# ESP32-_3_5_TFT_Display_SPI_V1_0_20230116.net
KiCad netlist of a schematic drawn in EAGLE
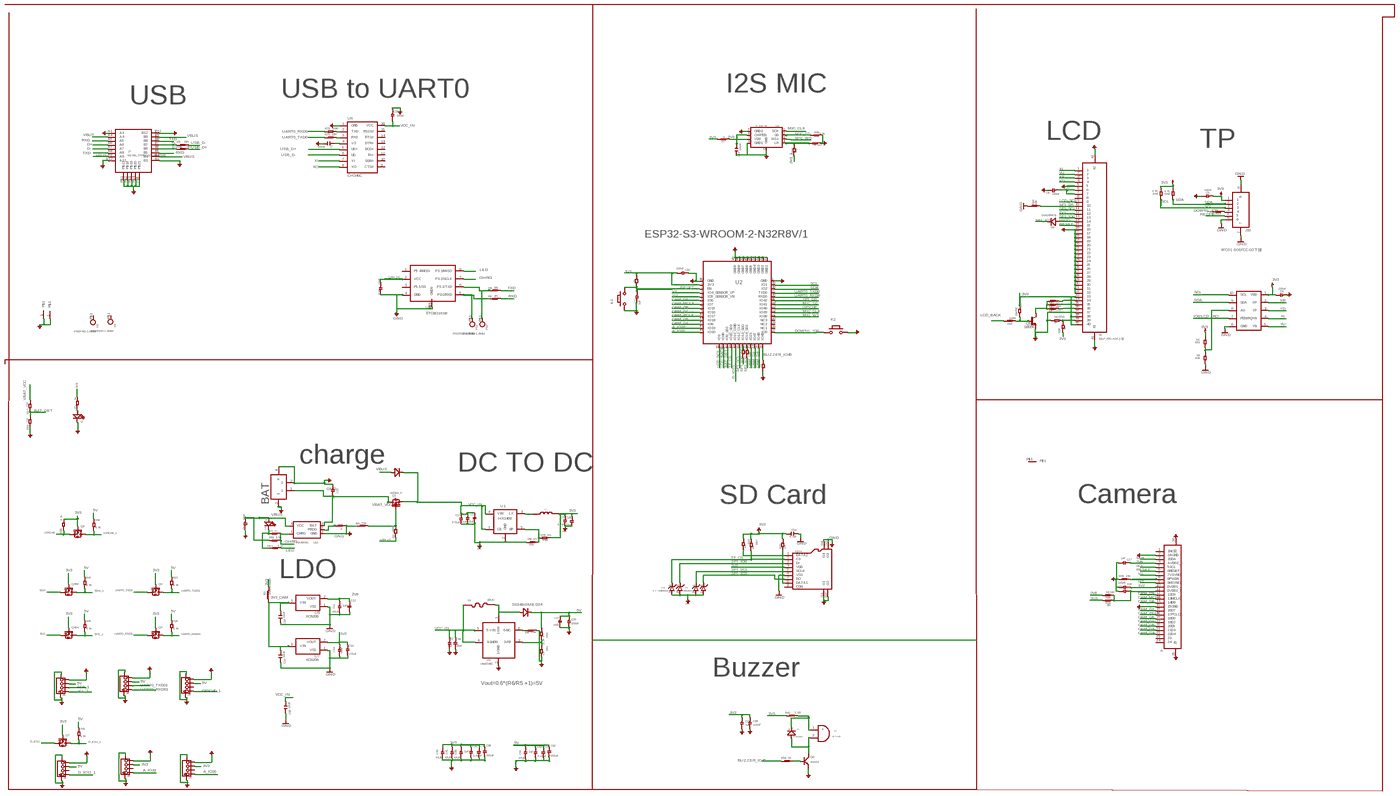
[diagram p0: schematic, sheet 1, overview]
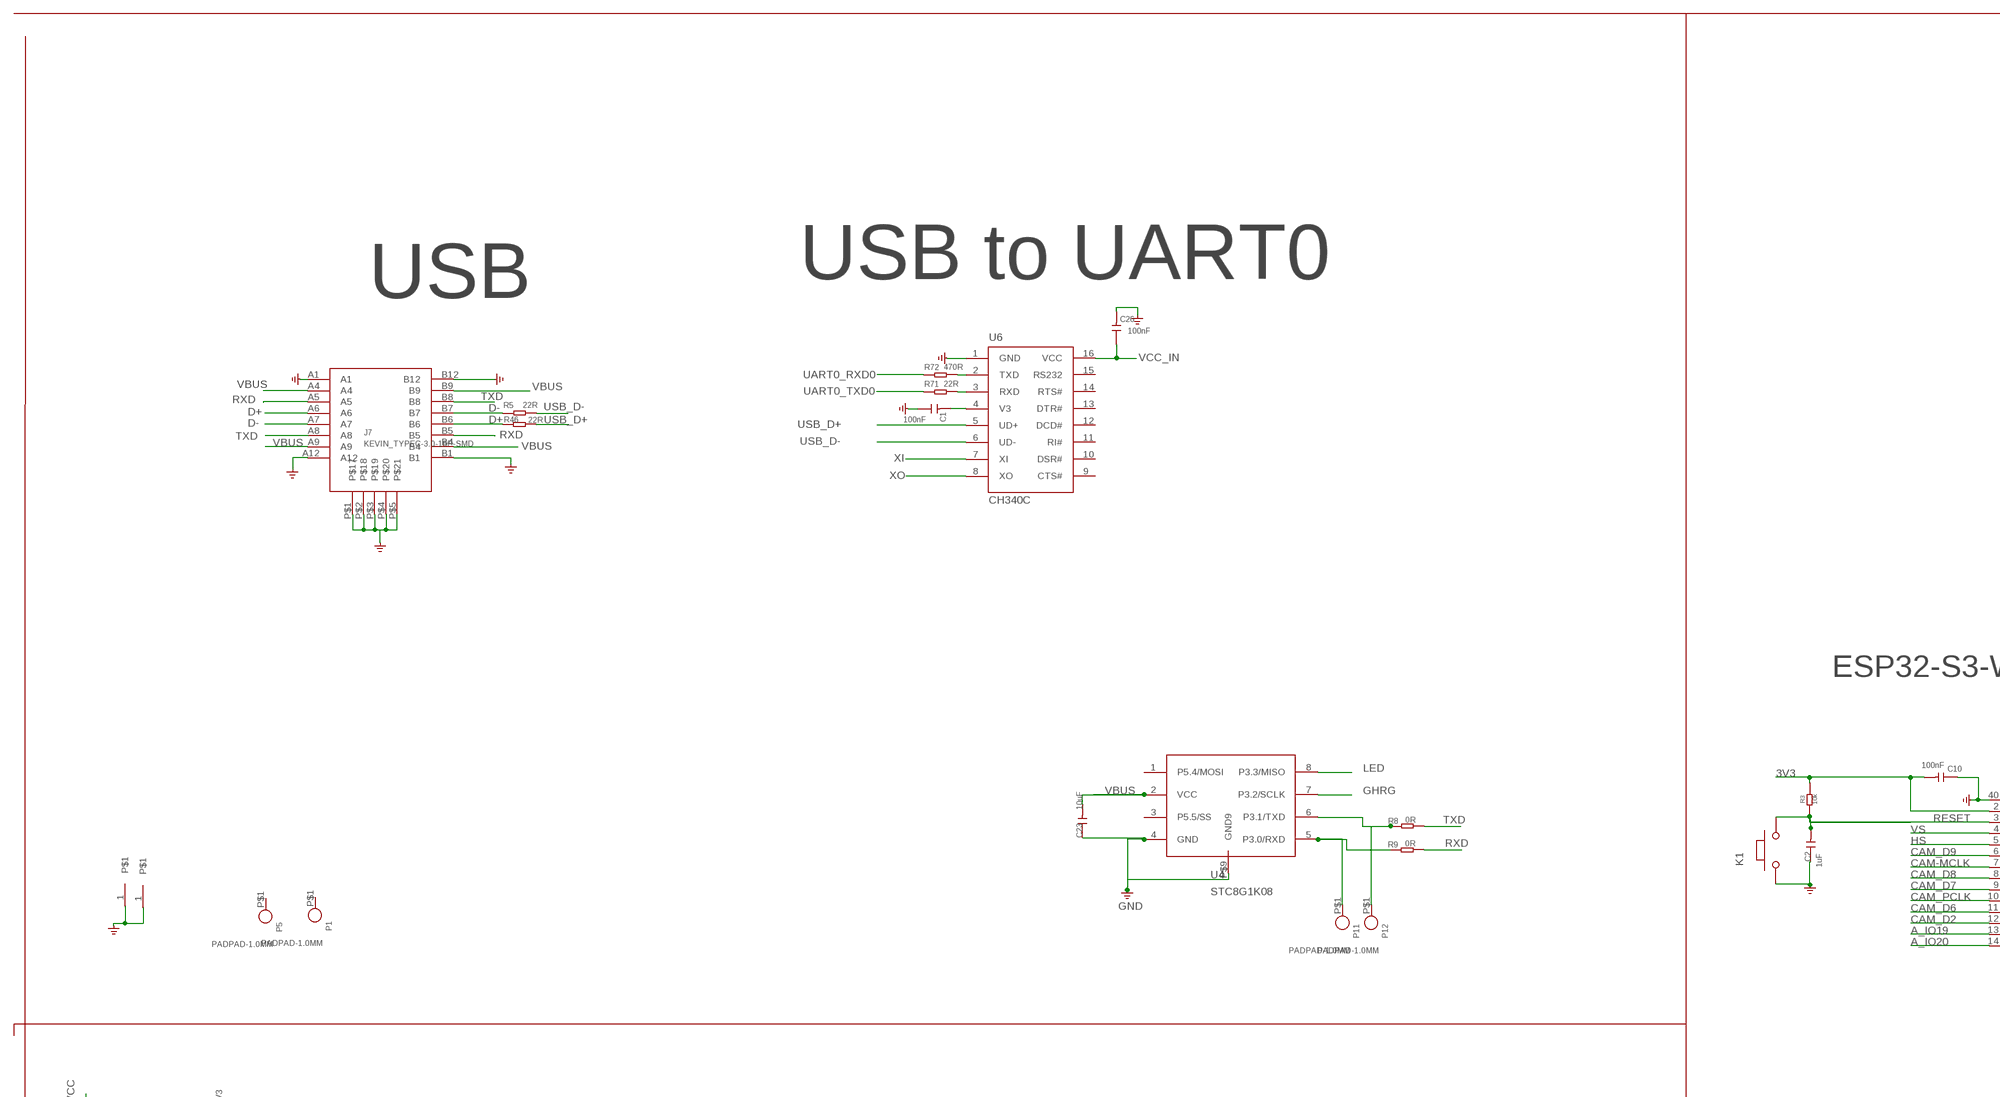
[diagram p1: schematic, sheet 1, part 1 of 4]
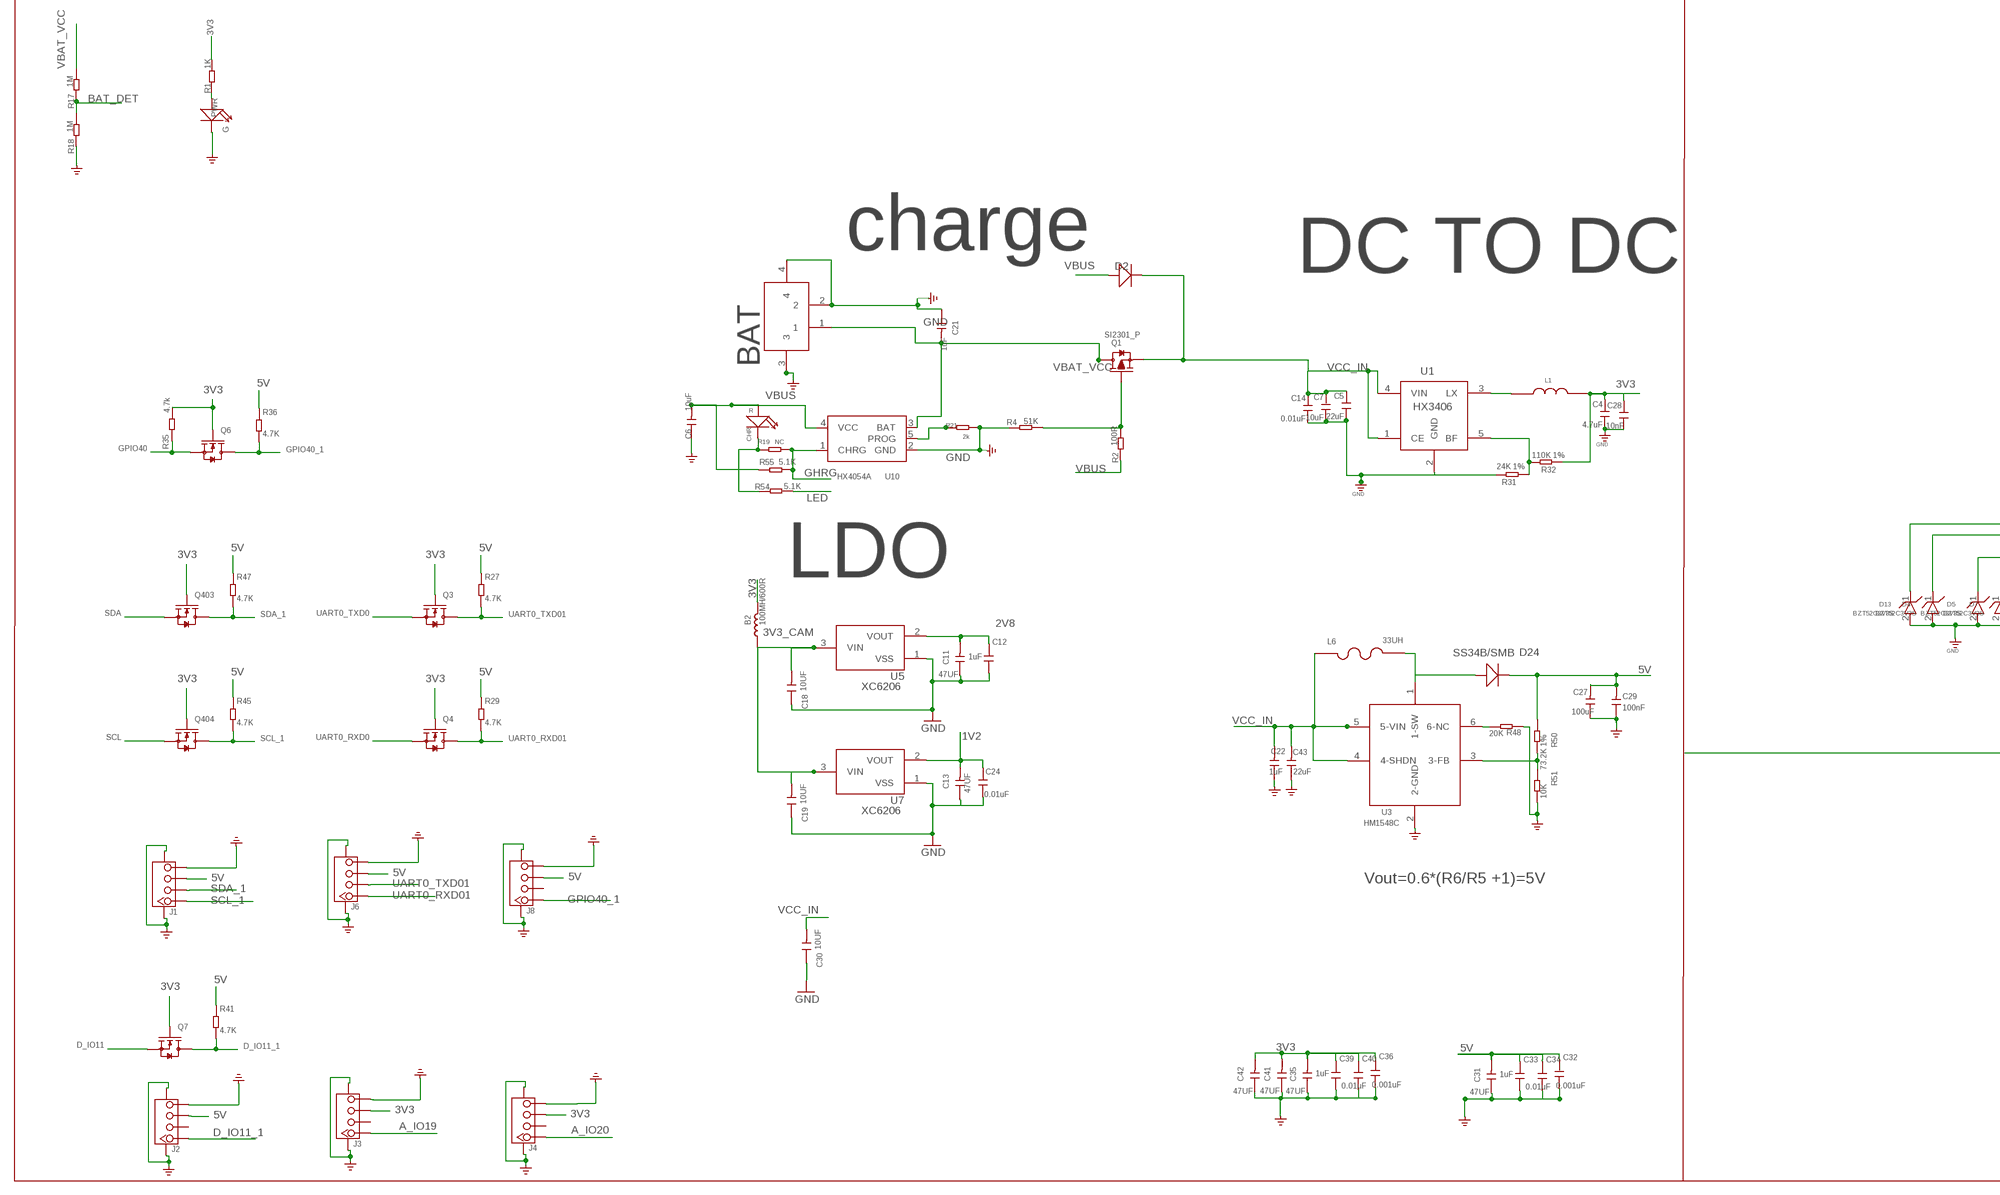
[diagram p2: schematic, sheet 1, part 2 of 4]
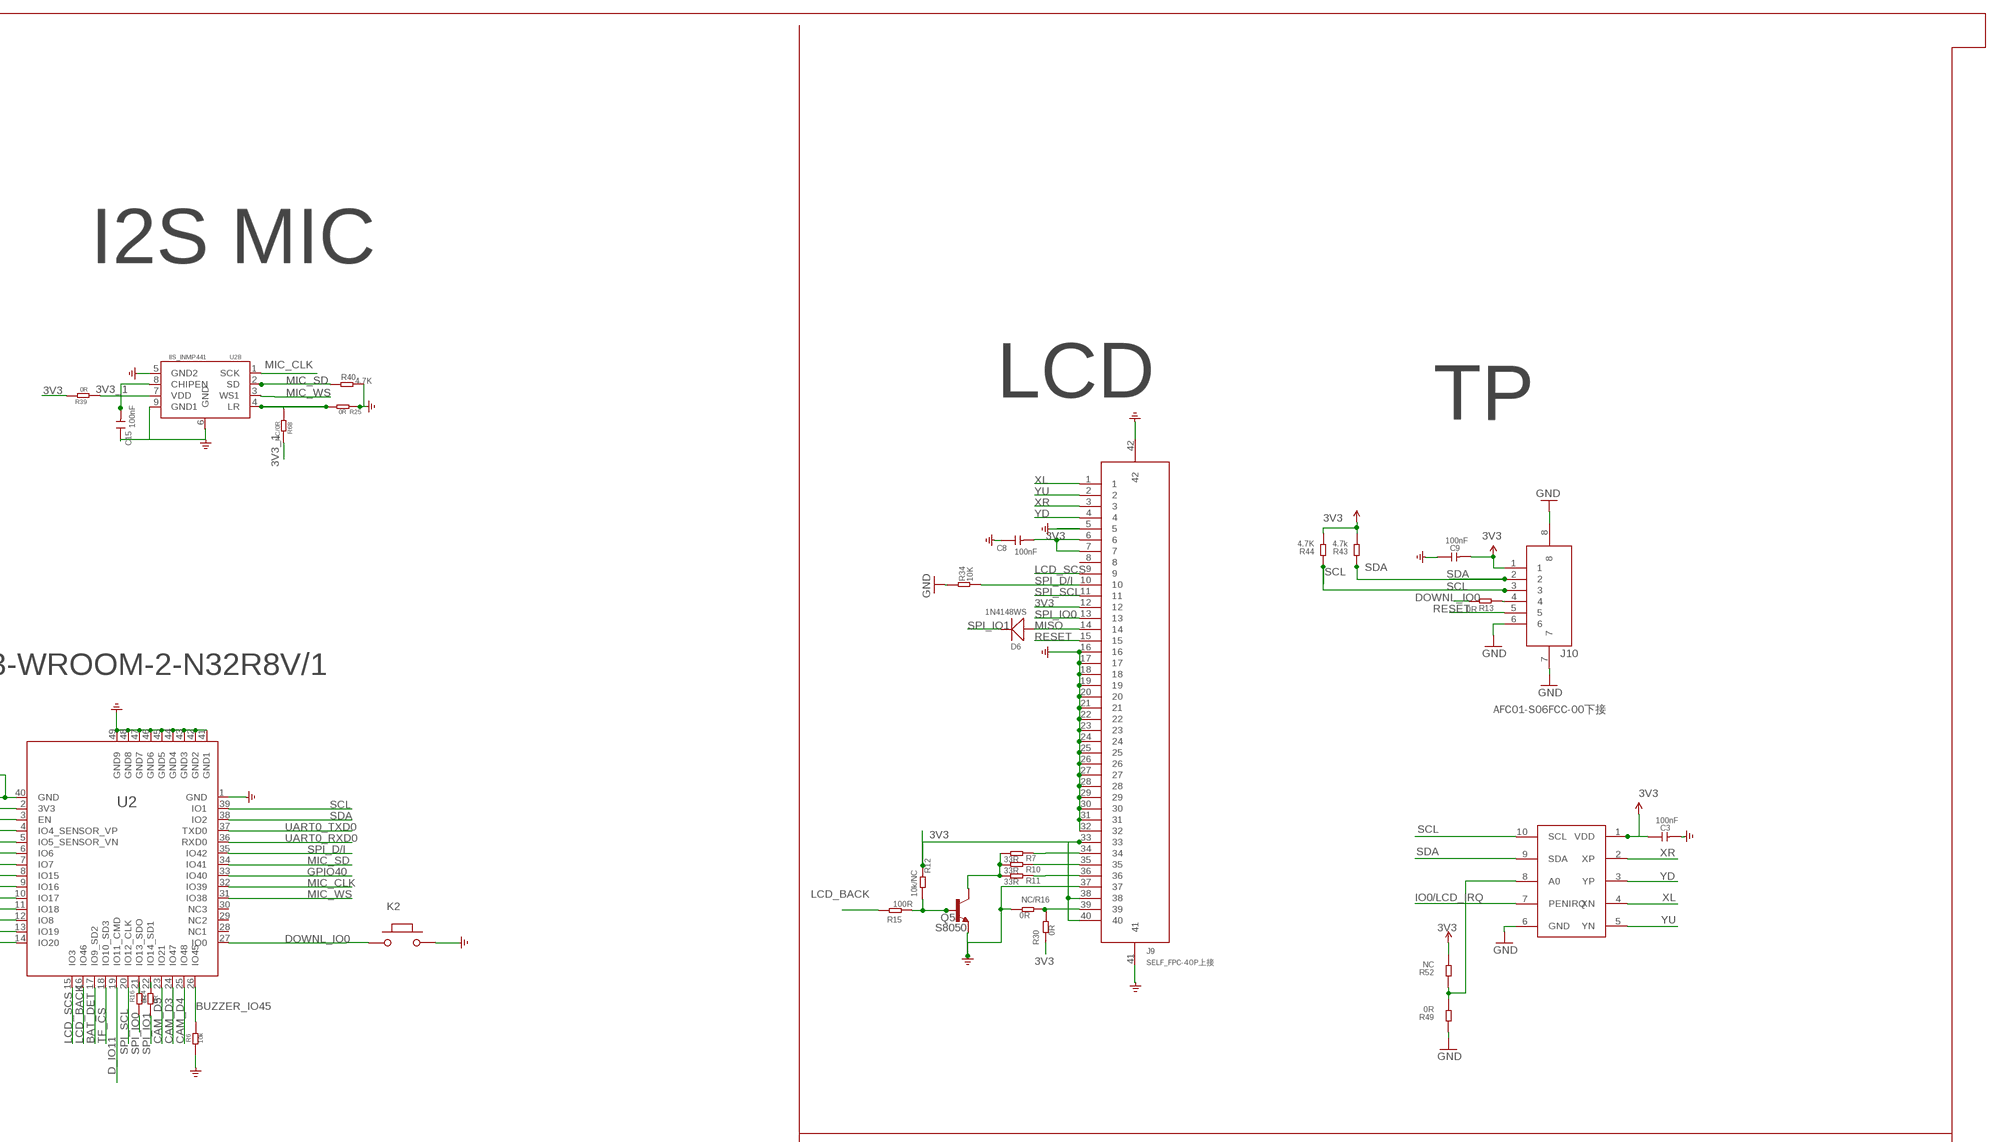
[diagram p3: schematic, sheet 1, part 3 of 4]
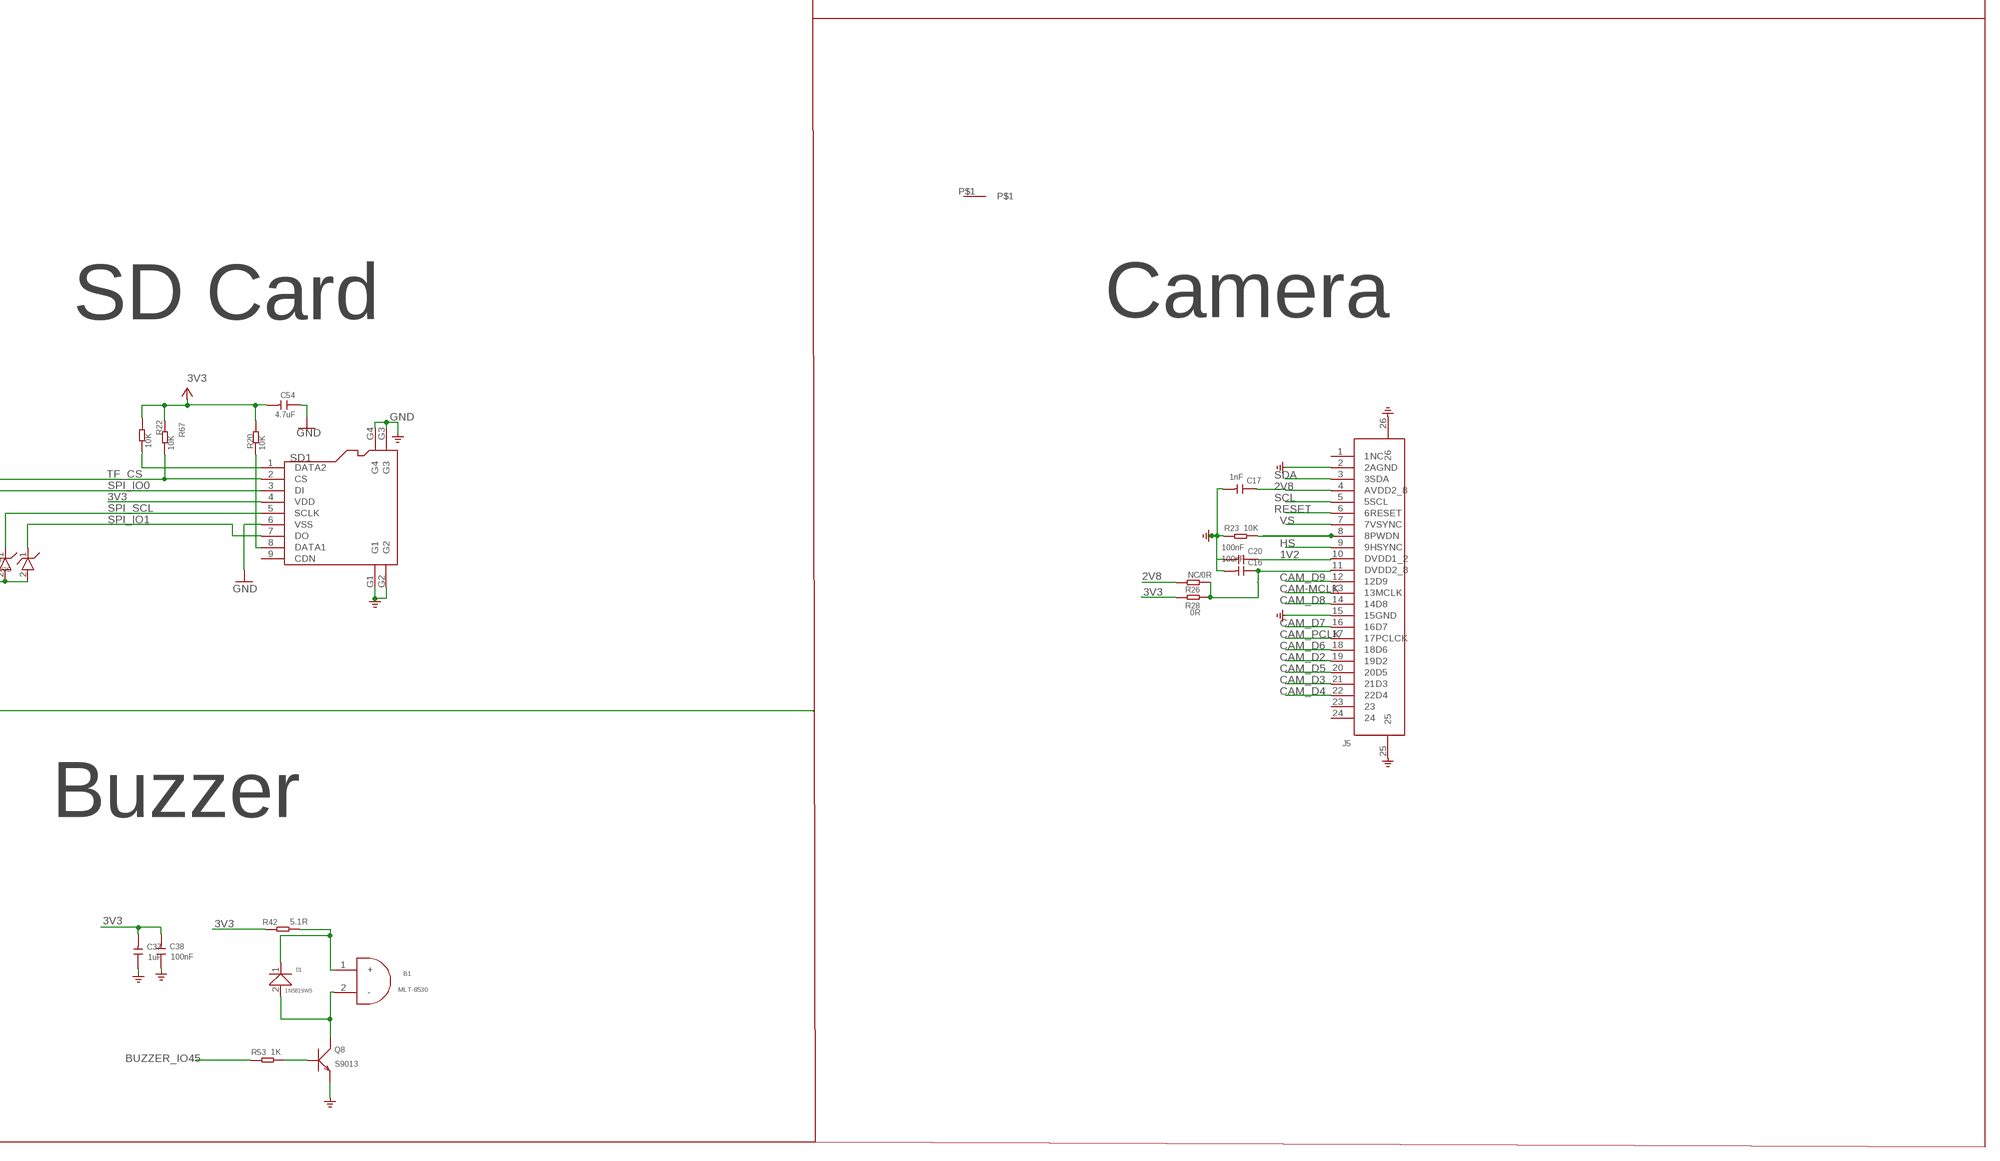
[diagram p4: schematic, sheet 1, part 4 of 4]

(export (version "E")
  (design (tool "Eeschema 10.0.6"))
  (components
    (comp (ref "B1")
      (value "MLT-8530")
      (footprint "eagle-import:MLT-8530")
      (libsource (lib "eagle-import") (part "MLT-8530"))
    )
    (comp (ref "B2")
      (value "100MH/600R")
      (footprint "eagle-import:0805@1")
      (libsource (lib "eagle-import") (part "L0805"))
    )
    (comp (ref "BAT")
      (value "CON-80-2P-M")
      (footprint "eagle-import:2P-2.0-M")
      (libsource (lib "eagle-import") (part "CON-80-2P-M"))
    )
    (comp (ref "C1")
      (value "100nF")
      (footprint "eagle-import:0603")
      (libsource (lib "eagle-import") (part "C0603"))
    )
    (comp (ref "C2")
      (value "1uF")
      (footprint "eagle-import:C0603")
      (libsource (lib "eagle-import") (part "C-0603"))
    )
    (comp (ref "C3")
      (value "100nF")
      (footprint "eagle-import:C0603")
      (libsource (lib "eagle-import") (part "C-0603"))
    )
    (comp (ref "C4")
      (value "4.7uF")
      (footprint "eagle-import:0603")
      (libsource (lib "eagle-import") (part "cooper_C0603"))
    )
    (comp (ref "C5")
      (value "22uF")
      (footprint "eagle-import:0603")
      (libsource (lib "eagle-import") (part "cooper_C0603"))
    )
    (comp (ref "C6")
      (value "10uF")
      (footprint "eagle-import:C0603")
      (libsource (lib "eagle-import") (part "C-0603"))
    )
    (comp (ref "C7")
      (value "10uF")
      (footprint "eagle-import:0603")
      (libsource (lib "eagle-import") (part "cooper_C0603"))
    )
    (comp (ref "C8")
      (value "100nF")
      (footprint "eagle-import:C0603")
      (libsource (lib "eagle-import") (part "C-0603"))
    )
    (comp (ref "C9")
      (value "100nF")
      (footprint "eagle-import:C0603")
      (libsource (lib "eagle-import") (part "C-0603"))
    )
    (comp (ref "C10")
      (value "100nF")
      (footprint "eagle-import:C0603")
      (libsource (lib "eagle-import") (part "C-0603"))
    )
    (comp (ref "C11")
      (value "47UF")
      (footprint "eagle-import:1206")
      (libsource (lib "eagle-import") (part "C1206"))
    )
    (comp (ref "C12")
      (value "1uF")
      (footprint "eagle-import:0603")
      (libsource (lib "eagle-import") (part "cooper_C0603"))
    )
    (comp (ref "C13")
      (value "47UF")
      (footprint "eagle-import:1206")
      (libsource (lib "eagle-import") (part "C1206"))
    )
    (comp (ref "C14")
      (value "0.01uF")
      (footprint "eagle-import:0603")
      (libsource (lib "eagle-import") (part "cooper_C0603"))
    )
    (comp (ref "C15")
      (value "100nF")
      (footprint "eagle-import:C0603")
      (libsource (lib "eagle-import") (part "C-0603"))
    )
    (comp (ref "C16")
      (value "100nF")
      (footprint "eagle-import:C0603")
      (libsource (lib "eagle-import") (part "C-0603"))
    )
    (comp (ref "C17")
      (value "1nF")
      (footprint "eagle-import:C0603")
      (libsource (lib "eagle-import") (part "C-0603"))
    )
    (comp (ref "C18")
      (value "10UF")
      (footprint "eagle-import:C0603")
      (libsource (lib "eagle-import") (part "C-0603"))
    )
    (comp (ref "C19")
      (value "10UF")
      (footprint "eagle-import:C0603")
      (libsource (lib "eagle-import") (part "C-0603"))
    )
    (comp (ref "C20")
      (value "100nF")
      (footprint "eagle-import:C0603")
      (libsource (lib "eagle-import") (part "C-0603"))
    )
    (comp (ref "C21")
      (value "1uF")
      (footprint "eagle-import:C0603")
      (libsource (lib "eagle-import") (part "C-0603"))
    )
    (comp (ref "C22")
      (value "1uF")
      (footprint "eagle-import:0603")
      (libsource (lib "eagle-import") (part "C0603"))
    )
    (comp (ref "C23")
      (value "10uF")
      (footprint "eagle-import:C0603")
      (libsource (lib "eagle-import") (part "C-0603"))
    )
    (comp (ref "C24")
      (value "0.01uF")
      (footprint "eagle-import:0603")
      (libsource (lib "eagle-import") (part "cooper_C0603"))
    )
    (comp (ref "C26")
      (value "100nF")
      (footprint "eagle-import:0603")
      (libsource (lib "eagle-import") (part "C0603"))
    )
    (comp (ref "C27")
      (value "100uF")
      (footprint "eagle-import:0805")
      (libsource (lib "eagle-import") (part "C0805"))
    )
    (comp (ref "C28")
      (value "10nF")
      (footprint "eagle-import:0603")
      (libsource (lib "eagle-import") (part "cooper_C0603"))
    )
    (comp (ref "C29")
      (value "100nF")
      (footprint "eagle-import:0603")
      (libsource (lib "eagle-import") (part "C0603"))
    )
    (comp (ref "C30")
      (value "10UF")
      (footprint "eagle-import:C0603")
      (libsource (lib "eagle-import") (part "C-0603"))
    )
    (comp (ref "C31")
      (value "47UF")
      (footprint "eagle-import:1206")
      (libsource (lib "eagle-import") (part "C1206"))
    )
    (comp (ref "C32")
      (value "0.001uF")
      (footprint "eagle-import:0603")
      (libsource (lib "eagle-import") (part "cooper_C0603"))
    )
    (comp (ref "C33")
      (value "1uF")
      (footprint "eagle-import:0603")
      (libsource (lib "eagle-import") (part "cooper_C0603"))
    )
    (comp (ref "C34")
      (value "0.01uF")
      (footprint "eagle-import:0603")
      (libsource (lib "eagle-import") (part "cooper_C0603"))
    )
    (comp (ref "C35")
      (value "47UF")
      (footprint "eagle-import:1206")
      (libsource (lib "eagle-import") (part "C1206"))
    )
    (comp (ref "C36")
      (value "0.001uF")
      (footprint "eagle-import:0603")
      (libsource (lib "eagle-import") (part "cooper_C0603"))
    )
    (comp (ref "C37")
      (value "1uF")
      (footprint "eagle-import:DISCRETE_C0603")
      (libsource (lib "eagle-import") (part "A_xbj_DISCRETE_C-0603"))
    )
    (comp (ref "C38")
      (value "100nF")
      (footprint "eagle-import:DISCRETE_C0603")
      (libsource (lib "eagle-import") (part "A_xbj_DISCRETE_C-0603"))
    )
    (comp (ref "C39")
      (value "1uF")
      (footprint "eagle-import:0603")
      (libsource (lib "eagle-import") (part "cooper_C0603"))
    )
    (comp (ref "C40")
      (value "0.01uF")
      (footprint "eagle-import:0603")
      (libsource (lib "eagle-import") (part "cooper_C0603"))
    )
    (comp (ref "C41")
      (value "47UF")
      (footprint "eagle-import:1206")
      (libsource (lib "eagle-import") (part "C1206"))
    )
    (comp (ref "C42")
      (value "47UF")
      (footprint "eagle-import:1206")
      (libsource (lib "eagle-import") (part "C1206"))
    )
    (comp (ref "C43")
      (value "22uF")
      (footprint "eagle-import:0805")
      (libsource (lib "eagle-import") (part "C0805"))
    )
    (comp (ref "C54")
      (value "4.7uF")
      (footprint "eagle-import:DISCRETE_C0603")
      (libsource (lib "eagle-import") (part "DISCRETE_C-0603"))
    )
    (comp (ref "CHR")
      (value "R")
      (footprint "eagle-import:D0603")
      (libsource (lib "eagle-import") (part "007-LED0603"))
    )
    (comp (ref "D1")
      (value "1N5819WS")
      (footprint "eagle-import:SOD-323")
      (libsource (lib "eagle-import") (part "1N5819WS"))
    )
    (comp (ref "D2")
      (value "1N5819/S0D-123")
      (footprint "eagle-import:1206-1")
      (libsource (lib "eagle-import") (part "D'1N4148-SMD'"))
    )
    (comp (ref "D4")
      (value "BZT52C3V3S")
      (footprint "eagle-import:SOD-323@1")
      (libsource (lib "eagle-import") (part "BZT52C3V3S"))
    )
    (comp (ref "D5")
      (value "BZT52C3V3S")
      (footprint "eagle-import:SOD-323@1")
      (libsource (lib "eagle-import") (part "BZT52C3V3S"))
    )
    (comp (ref "D6")
      (value "1N4148WS")
      (footprint "eagle-import:SOD323")
      (libsource (lib "eagle-import") (part "D'0805'"))
    )
    (comp (ref "D7")
      (value "BZT52C3V3S")
      (footprint "eagle-import:SOD-323@1")
      (libsource (lib "eagle-import") (part "BZT52C3V3S"))
    )
    (comp (ref "D13")
      (value "BZT52C3V3S")
      (footprint "eagle-import:SOD-323@1")
      (libsource (lib "eagle-import") (part "BZT52C3V3S"))
    )
    (comp (ref "D24")
      (value "SS34B/SMB")
      (footprint "eagle-import:214AB")
      (libsource (lib "eagle-import") (part "214ABDO-214AB"))
    )
    (comp (ref "J1")
      (value "TWIG-4P-2.0-SMD-FEMALE-REINFORCE'90D'")
      (footprint "eagle-import:4P-SMD-2.0-90D")
      (libsource (lib "eagle-import") (part "TWIG-4P-2.0-SMD-FEMALE-REINFORCE'90D'"))
    )
    (comp (ref "J2")
      (value "TWIG-4P-2.0-SMD-FEMALE-REINFORCE'90D'")
      (footprint "eagle-import:4P-SMD-2.0-90D")
      (libsource (lib "eagle-import") (part "TWIG-4P-2.0-SMD-FEMALE-REINFORCE'90D'"))
    )
    (comp (ref "J3")
      (value "TWIG-4P-2.0-SMD-FEMALE-REINFORCE'90D'")
      (footprint "eagle-import:4P-SMD-2.0-90D")
      (libsource (lib "eagle-import") (part "TWIG-4P-2.0-SMD-FEMALE-REINFORCE'90D'"))
    )
    (comp (ref "J4")
      (value "TWIG-4P-2.0-SMD-FEMALE-REINFORCE'90D'")
      (footprint "eagle-import:4P-SMD-2.0-90D")
      (libsource (lib "eagle-import") (part "TWIG-4P-2.0-SMD-FEMALE-REINFORCE'90D'"))
    )
    (comp (ref "J5")
      (value "SMD_HEADERP_24PX0.5上接")
      (footprint "eagle-import:SMD_HEADERP_24PX0.5")
      (libsource (lib "eagle-import") (part "SMD_HEADERP_24PX0.5"))
    )
    (comp (ref "J6")
      (value "TWIG-4P-2.0-SMD-FEMALE-REINFORCE'90D'")
      (footprint "eagle-import:4P-SMD-2.0-90D")
      (libsource (lib "eagle-import") (part "TWIG-4P-2.0-SMD-FEMALE-REINFORCE'90D'"))
    )
    (comp (ref "J7")
      (value "KEVIN_TYPEC-3.0-16P-SMD")
      (footprint "eagle-import:KEVIN_3.0TYPEC-SMD")
      (libsource (lib "eagle-import") (part "KEVIN_TYPEC-3.0-16P-SMD"))
    )
    (comp (ref "J8")
      (value "TWIG-4P-2.0-SMD-FEMALE-REINFORCE'90D'")
      (footprint "eagle-import:4P-SMD-2.0-90D")
      (libsource (lib "eagle-import") (part "TWIG-4P-2.0-SMD-FEMALE-REINFORCE'90D'"))
    )
    (comp (ref "J9")
      (value "SELF_FPC-40P上接")
      (footprint "eagle-import:SELF_SMD42-50P-2560L490W")
      (libsource (lib "eagle-import") (part "SELF_FPC-40P"))
    )
    (comp (ref "J10")
      (value "AFC01-S06FCC-00下接")
      (footprint "eagle-import:SMD8-50P-740L535W")
      (libsource (lib "eagle-import") (part "AFC01-S06FCC-00"))
    )
    (comp (ref "K1")
      (value "BUTTON")
      (footprint "eagle-import:157SW")
      (libsource (lib "eagle-import") (part "PB157"))
    )
    (comp (ref "K2")
      (value "BUTTON")
      (footprint "eagle-import:157SW")
      (libsource (lib "eagle-import") (part "PB157"))
    )
    (comp (ref "L1")
      (value "CD32_10uH")
      (footprint "eagle-import:CD32")
      (libsource (lib "eagle-import") (part "CD32_950MA"))
    )
    (comp (ref "L6")
      (value "33UH")
      (footprint "eagle-import:L773")
      (libsource (lib "eagle-import") (part "L-773"))
    )
    (comp (ref "NC/R16")
      (value "0R")
      (footprint "eagle-import:R0603")
      (libsource (lib "eagle-import") (part "cooper_R0603"))
    )
    (comp (ref "P1")
      (value "PADPAD-1.0MM")
      (footprint "eagle-import:PAD-1.0MM")
      (libsource (lib "eagle-import") (part "PADPAD-1.0MM"))
    )
    (comp (ref "P3")
      (value "3M-5")
      (footprint "eagle-import:3M-5")
      (libsource (lib "eagle-import") (part "3M-5"))
    )
    (comp (ref "P4")
      (value "3M-5")
      (footprint "eagle-import:3M-5")
      (libsource (lib "eagle-import") (part "3M-5"))
    )
    (comp (ref "P5")
      (value "PADPAD-1.0MM")
      (footprint "eagle-import:PAD-1.0MM")
      (libsource (lib "eagle-import") (part "PADPAD-1.0MM"))
    )
    (comp (ref "P11")
      (value "PADPAD-1.0MM")
      (footprint "eagle-import:PAD-1.0MM")
      (libsource (lib "eagle-import") (part "PADPAD-1.0MM"))
    )
    (comp (ref "P12")
      (value "PADPAD-1.0MM")
      (footprint "eagle-import:PAD-1.0MM")
      (libsource (lib "eagle-import") (part "PADPAD-1.0MM"))
    )
    (comp (ref "PWR")
      (value "G")
      (footprint "eagle-import:LED-0603")
      (libsource (lib "eagle-import") (part "LED'0603'"))
    )
    (comp (ref "Q1")
      (value "SI2301_P")
      (footprint "eagle-import:DISCRETE_SOT23")
      (libsource (lib "eagle-import") (part "DISCRETE_MOSFET-PSOT23"))
    )
    (comp (ref "Q3")
      (value "MOSFET-N'SOT23'")
      (footprint "eagle-import:SOT23")
      (libsource (lib "eagle-import") (part "MOSFET-N'SOT23'"))
    )
    (comp (ref "Q4")
      (value "MOSFET-N'SOT23'")
      (footprint "eagle-import:SOT23")
      (libsource (lib "eagle-import") (part "MOSFET-N'SOT23'"))
    )
    (comp (ref "Q5")
      (value "S8050")
      (footprint "eagle-import:SPARKFUN_SOT23")
      (libsource (lib "eagle-import") (part "SPARKFUN_TRANSISTOR_NPNSOT23"))
    )
    (comp (ref "Q6")
      (value "MOSFET-N'SOT23'")
      (footprint "eagle-import:SOT23")
      (libsource (lib "eagle-import") (part "MOSFET-N'SOT23'"))
    )
    (comp (ref "Q7")
      (value "MOSFET-N'SOT23'")
      (footprint "eagle-import:SOT23")
      (libsource (lib "eagle-import") (part "MOSFET-N'SOT23'"))
    )
    (comp (ref "Q8")
      (value "S9013")
      (footprint "eagle-import:SOT23@1")
      (libsource (lib "eagle-import") (part "TRANSISTOR-NPN-SOT23"))
    )
    (comp (ref "Q403")
      (value "MOSFET-N'SOT23'")
      (footprint "eagle-import:SOT23")
      (libsource (lib "eagle-import") (part "MOSFET-N'SOT23'"))
    )
    (comp (ref "Q404")
      (value "MOSFET-N'SOT23'")
      (footprint "eagle-import:SOT23")
      (libsource (lib "eagle-import") (part "MOSFET-N'SOT23'"))
    )
    (comp (ref "R1")
      (value "1K")
      (footprint "eagle-import:R0603")
      (libsource (lib "eagle-import") (part "R-0603"))
    )
    (comp (ref "R2")
      (value "100R")
      (footprint "eagle-import:R0603")
      (libsource (lib "eagle-import") (part "cooper_R0603"))
    )
    (comp (ref "R3")
      (value "10k")
      (footprint "eagle-import:R0603")
      (libsource (lib "eagle-import") (part "R-0603"))
    )
    (comp (ref "R4")
      (value "51K")
      (footprint "eagle-import:R0603")
      (libsource (lib "eagle-import") (part "cooper_R0603"))
    )
    (comp (ref "R5")
      (value "22R")
      (footprint "eagle-import:DISCRETE_R0603")
      (libsource (lib "eagle-import") (part "Crowtail-_LED-V2.0-20190615-01_DISCRETE_R-0603"))
    )
    (comp (ref "R6")
      (value "10k")
      (footprint "eagle-import:R0603")
      (libsource (lib "eagle-import") (part "R-0603"))
    )
    (comp (ref "R7")
      (value "33R")
      (footprint "eagle-import:R0603")
      (libsource (lib "eagle-import") (part "cooper_R0603"))
    )
    (comp (ref "R8")
      (value "0R")
      (footprint "eagle-import:R0603")
      (libsource (lib "eagle-import") (part "cooper_R0603"))
    )
    (comp (ref "R9")
      (value "0R")
      (footprint "eagle-import:R0603")
      (libsource (lib "eagle-import") (part "cooper_R0603"))
    )
    (comp (ref "R10")
      (value "33R")
      (footprint "eagle-import:R0603")
      (libsource (lib "eagle-import") (part "cooper_R0603"))
    )
    (comp (ref "R11")
      (value "33R")
      (footprint "eagle-import:R0603")
      (libsource (lib "eagle-import") (part "cooper_R0603"))
    )
    (comp (ref "R12")
      (value "10k/NC")
      (footprint "eagle-import:R0603")
      (libsource (lib "eagle-import") (part "cooper_R0603"))
    )
    (comp (ref "R13")
      (value "0R")
      (footprint "eagle-import:DISCRETE_R0603")
      (libsource (lib "eagle-import") (part "DISCRETE_R-0603"))
    )
    (comp (ref "R15")
      (value "100R")
      (footprint "eagle-import:R0603")
      (libsource (lib "eagle-import") (part "cooper_R0603"))
    )
    (comp (ref "R16")
      (value "0R")
      (footprint "eagle-import:R0603")
      (libsource (lib "eagle-import") (part "R-0603"))
    )
    (comp (ref "R17")
      (value "1M")
      (footprint "eagle-import:R0603")
      (libsource (lib "eagle-import") (part "cooper_R0603"))
    )
    (comp (ref "R18")
      (value "1M")
      (footprint "eagle-import:R0603")
      (libsource (lib "eagle-import") (part "cooper_R0603"))
    )
    (comp (ref "R19")
      (value "NC")
      (footprint "eagle-import:R0603")
      (libsource (lib "eagle-import") (part "R-0603"))
    )
    (comp (ref "R20")
      (value "10K")
      (footprint "eagle-import:DISCRETE_R0603")
      (libsource (lib "eagle-import") (part "Crowtail-_LED-V2.0-20190615-01_DISCRETE_R-0603"))
    )
    (comp (ref "R21")
      (value "2k")
      (footprint "eagle-import:R0603")
      (libsource (lib "eagle-import") (part "R-0603"))
    )
    (comp (ref "R22")
      (value "10K")
      (footprint "eagle-import:DISCRETE_R0603")
      (libsource (lib "eagle-import") (part "Crowtail-_LED-V2.0-20190615-01_DISCRETE_R-0603"))
    )
    (comp (ref "R23")
      (value "10K")
      (footprint "eagle-import:DISCRETE_R0603")
      (libsource (lib "eagle-import") (part "Crowtail-_LED-V2.0-20190615-01_DISCRETE_R-0603"))
    )
    (comp (ref "R24")
      (value "0R")
      (footprint "eagle-import:R0603")
      (libsource (lib "eagle-import") (part "R-0603"))
    )
    (comp (ref "R25")
      (value "0R")
      (footprint "eagle-import:R0603")
      (libsource (lib "eagle-import") (part "R-0603"))
    )
    (comp (ref "R26")
      (value "NC/0R")
      (footprint "eagle-import:R0603")
      (libsource (lib "eagle-import") (part "cooper_R0603"))
    )
    (comp (ref "R27")
      (value "4.7K")
      (footprint "eagle-import:R0603")
      (libsource (lib "eagle-import") (part "cooper_R0603"))
    )
    (comp (ref "R28")
      (value "0R")
      (footprint "eagle-import:R0603")
      (libsource (lib "eagle-import") (part "cooper_R0603"))
    )
    (comp (ref "R29")
      (value "4.7K")
      (footprint "eagle-import:R0603")
      (libsource (lib "eagle-import") (part "cooper_R0603"))
    )
    (comp (ref "R30")
      (value "0R")
      (footprint "eagle-import:R0603")
      (libsource (lib "eagle-import") (part "cooper_R0603"))
    )
    (comp (ref "R31")
      (value "24K 1%")
      (footprint "eagle-import:R0603")
      (libsource (lib "eagle-import") (part "cooper_R0603"))
    )
    (comp (ref "R32")
      (value "110K 1%")
      (footprint "eagle-import:R0603")
      (libsource (lib "eagle-import") (part "cooper_R0603"))
    )
    (comp (ref "R34")
      (value "10K")
      (footprint "eagle-import:DISCRETE_R0603")
      (libsource (lib "eagle-import") (part "DISCRETE_R-0603"))
    )
    (comp (ref "R35")
      (value "4.7k")
      (footprint "eagle-import:R0603")
      (libsource (lib "eagle-import") (part "cooper_R0603"))
    )
    (comp (ref "R36")
      (value "4.7K")
      (footprint "eagle-import:R0603")
      (libsource (lib "eagle-import") (part "cooper_R0603"))
    )
    (comp (ref "R39")
      (value "0R")
      (footprint "eagle-import:R0603")
      (libsource (lib "eagle-import") (part "R-0603"))
    )
    (comp (ref "R40")
      (value "4.7K")
      (footprint "eagle-import:DISCRETE_R0603")
      (libsource (lib "eagle-import") (part "Crowtail-_LED-V2.0-20190615-01_DISCRETE_R-0603"))
    )
    (comp (ref "R41")
      (value "4.7K")
      (footprint "eagle-import:R0603")
      (libsource (lib "eagle-import") (part "cooper_R0603"))
    )
    (comp (ref "R42")
      (value "5.1R")
      (footprint "eagle-import:R0603")
      (libsource (lib "eagle-import") (part "R0603"))
    )
    (comp (ref "R43")
      (value "4.7k")
      (footprint "eagle-import:DISCRETE_R0603")
      (libsource (lib "eagle-import") (part "DISCRETE_R-0603"))
    )
    (comp (ref "R44")
      (value "4.7K")
      (footprint "eagle-import:DISCRETE_R0603")
      (libsource (lib "eagle-import") (part "DISCRETE_R-0603"))
    )
    (comp (ref "R45")
      (value "4.7K")
      (footprint "eagle-import:R0603")
      (libsource (lib "eagle-import") (part "cooper_R0603"))
    )
    (comp (ref "R46")
      (value "22R")
      (footprint "eagle-import:DISCRETE_R0603")
      (libsource (lib "eagle-import") (part "Crowtail-_LED-V2.0-20190615-01_DISCRETE_R-0603"))
    )
    (comp (ref "R47")
      (value "4.7K")
      (footprint "eagle-import:R0603")
      (libsource (lib "eagle-import") (part "cooper_R0603"))
    )
    (comp (ref "R48")
      (value "20K")
      (footprint "eagle-import:DISCRETE_R0603")
      (libsource (lib "eagle-import") (part "Crowtail-_LED-V2.0-20190615-01_DISCRETE_R-0603"))
    )
    (comp (ref "R49")
      (value "0R")
      (footprint "eagle-import:DISCRETE_R0603")
      (libsource (lib "eagle-import") (part "DISCRETE_R-0603"))
    )
    (comp (ref "R50")
      (value "73.2K 1%")
      (footprint "eagle-import:DISCRETE_R0603")
      (libsource (lib "eagle-import") (part "Crowtail-_LED-V2.0-20190615-01_DISCRETE_R-0603"))
    )
    (comp (ref "R51")
      (value "10K")
      (footprint "eagle-import:DISCRETE_R0603")
      (libsource (lib "eagle-import") (part "Crowtail-_LED-V2.0-20190615-01_DISCRETE_R-0603"))
    )
    (comp (ref "R52")
      (value "NC")
      (footprint "eagle-import:DISCRETE_R0603")
      (libsource (lib "eagle-import") (part "DISCRETE_R-0603"))
    )
    (comp (ref "R53")
      (value "1K")
      (footprint "eagle-import:DISCRETE_R0603")
      (libsource (lib "eagle-import") (part "Crowtail-_LED-V2.0-20190615-01_DISCRETE_R-0603"))
    )
    (comp (ref "R54")
      (value "5.1K")
      (footprint "eagle-import:DISCRETE_R0603")
      (libsource (lib "eagle-import") (part "Crowtail-_LED-V2.0-20190615-01_DISCRETE_R-0603"))
    )
    (comp (ref "R55")
      (value "5.1K")
      (footprint "eagle-import:DISCRETE_R0603")
      (libsource (lib "eagle-import") (part "Crowtail-_LED-V2.0-20190615-01_DISCRETE_R-0603"))
    )
    (comp (ref "R67")
      (value "10K")
      (footprint "eagle-import:DISCRETE_R0603")
      (libsource (lib "eagle-import") (part "Crowtail-_LED-V2.0-20190615-01_DISCRETE_R-0603"))
    )
    (comp (ref "R68")
      (value "NC/0R")
      (footprint "eagle-import:R0603")
      (libsource (lib "eagle-import") (part "R-0603"))
    )
    (comp (ref "R71")
      (value "22R")
      (footprint "eagle-import:DISCRETE_R0603")
      (libsource (lib "eagle-import") (part "Crowtail-_LED-V2.0-20190615-01_DISCRETE_R-0603"))
    )
    (comp (ref "R72")
      (value "470R")
      (footprint "eagle-import:DISCRETE_R0603")
      (libsource (lib "eagle-import") (part "Crowtail-_LED-V2.0-20190615-01_DISCRETE_R-0603"))
    )
    (comp (ref "SD1")
      (value "HOLDER-MICROSD-9P")
      (footprint "eagle-import:9P-SMD-W_-RING")
      (libsource (lib "eagle-import") (part "HOLDER-MICROSD-9P"))
    )
    (comp (ref "U$63")
      (value "TFT-3.5")
      (footprint "eagle-import:LCD3.5寸")
      (libsource (lib "eagle-import") (part "TFT-3.5"))
    )
    (comp (ref "U1")
      (value "HX3406")
      (footprint "eagle-import:SOT23-5")
      (libsource (lib "eagle-import") (part "HX3406"))
    )
    (comp (ref "U2")
      (value "ESP32-S3-WROOM-2-N32R8V/1")
      (footprint "eagle-import:ESP32-S3-WROOM-2-N32R8V_1")
      (libsource (lib "eagle-import") (part "ESP32-S3-WROOM-2-N32R8V/1"))
    )
    (comp (ref "U3")
      (value "HM1548C")
      (footprint "eagle-import:A_XBJ_SOT23-6")
      (libsource (lib "eagle-import") (part "HM1548/SOT23-6"))
    )
    (comp (ref "U4")
      (value "STC8G1K08")
      (footprint "eagle-import:DFN8")
      (libsource (lib "eagle-import") (part "STC8G1K08"))
    )
    (comp (ref "U5")
      (value "XC6206")
      (footprint "eagle-import:SOT-23")
      (libsource (lib "eagle-import") (part "XC6206"))
    )
    (comp (ref "U6")
      (value "CH340C")
      (footprint "eagle-import:SOP-16")
      (libsource (lib "eagle-import") (part "CH340G"))
    )
    (comp (ref "U7")
      (value "XC6206")
      (footprint "eagle-import:SOT-23")
      (libsource (lib "eagle-import") (part "XC6206"))
    )
    (comp (ref "U8")
      (value "NS2009")
      (footprint "eagle-import:MSOP10")
      (libsource (lib "eagle-import") (part "NS2009"))
    )
    (comp (ref "U10")
      (value "HX4054A")
      (footprint "eagle-import:HX4054A_SOT23_5")
      (libsource (lib "eagle-import") (part "HX4054A"))
    )
    (comp (ref "U28")
      (value "IIS_INMP441")
      (footprint "eagle-import:IIS_INMP441")
      (libsource (lib "eagle-import") (part "IIS_INMP441"))
    )
  )
  (nets
    (net (code "1") (name "+3V3") (class "Default")
      (node (ref "B2") (pin "2") (pinfunction "2_2") (pintype "passive"))
      (node (ref "C10") (pin "2") (pinfunction "2_2") (pintype "passive"))
      (node (ref "C28") (pin "1") (pinfunction "1_1") (pintype "passive"))
      (node (ref "C3") (pin "1") (pinfunction "1_1") (pintype "passive"))
      (node (ref "C35") (pin "2") (pinfunction "2_2") (pintype "passive"))
      (node (ref "C36") (pin "1") (pinfunction "1_1") (pintype "passive"))
      (node (ref "C37") (pin "2") (pinfunction "2_2") (pintype "passive"))
      (node (ref "C38") (pin "2") (pinfunction "2_2") (pintype "passive"))
      (node (ref "C39") (pin "1") (pinfunction "1_1") (pintype "passive"))
      (node (ref "C4") (pin "1") (pinfunction "1_1") (pintype "passive"))
      (node (ref "C40") (pin "1") (pinfunction "1_1") (pintype "passive"))
      (node (ref "C41") (pin "2") (pinfunction "2_2") (pintype "passive"))
      (node (ref "C42") (pin "2") (pinfunction "2_2") (pintype "passive"))
      (node (ref "C54") (pin "2") (pinfunction "2_2") (pintype "passive"))
      (node (ref "C8") (pin "2") (pinfunction "2_2") (pintype "passive"))
      (node (ref "C9") (pin "2") (pinfunction "2_2") (pintype "passive"))
      (node (ref "J10") (pin "1") (pinfunction "1_1") (pintype "bidirectional"))
      (node (ref "J3") (pin "3") (pinfunction "3_3") (pintype "bidirectional"))
      (node (ref "J4") (pin "3") (pinfunction "3_3") (pintype "bidirectional"))
      (node (ref "J9") (pin "12") (pinfunction "12_12") (pintype "bidirectional"))
      (node (ref "J9") (pin "33") (pinfunction "33_33") (pintype "bidirectional"))
      (node (ref "J9") (pin "38") (pinfunction "38_38") (pintype "bidirectional"))
      (node (ref "J9") (pin "40") (pinfunction "40_40") (pintype "bidirectional"))
      (node (ref "J9") (pin "6") (pinfunction "6_6") (pintype "bidirectional"))
      (node (ref "J9") (pin "7") (pinfunction "7_7") (pintype "bidirectional"))
      (node (ref "L1") (pin "2") (pinfunction "2_2") (pintype "bidirectional"))
      (node (ref "Q3") (pin "1") (pinfunction "G_1") (pintype "passive"))
      (node (ref "Q4") (pin "1") (pinfunction "G_1") (pintype "passive"))
      (node (ref "Q403") (pin "1") (pinfunction "G_1") (pintype "passive"))
      (node (ref "Q404") (pin "1") (pinfunction "G_1") (pintype "passive"))
      (node (ref "Q6") (pin "1") (pinfunction "G_1") (pintype "passive"))
      (node (ref "Q7") (pin "1") (pinfunction "G_1") (pintype "passive"))
      (node (ref "R1") (pin "2") (pinfunction "2_2") (pintype "passive"))
      (node (ref "R12") (pin "2") (pinfunction "2_2") (pintype "passive"))
      (node (ref "R20") (pin "1") (pinfunction "1_1") (pintype "passive"))
      (node (ref "R22") (pin "1") (pinfunction "1_1") (pintype "passive"))
      (node (ref "R28") (pin "2") (pinfunction "2_2") (pintype "passive"))
      (node (ref "R3") (pin "2") (pinfunction "2_2") (pintype "passive"))
      (node (ref "R30") (pin "1") (pinfunction "1_1") (pintype "passive"))
      (node (ref "R32") (pin "2") (pinfunction "2_2") (pintype "passive"))
      (node (ref "R35") (pin "2") (pinfunction "2_2") (pintype "passive"))
      (node (ref "R39") (pin "2") (pinfunction "2_2") (pintype "passive"))
      (node (ref "R42") (pin "1") (pinfunction "1_1") (pintype "passive"))
      (node (ref "R43") (pin "2") (pinfunction "2_2") (pintype "passive"))
      (node (ref "R44") (pin "2") (pinfunction "2_2") (pintype "passive"))
      (node (ref "R52") (pin "2") (pinfunction "2_2") (pintype "passive"))
      (node (ref "R67") (pin "1") (pinfunction "1_1") (pintype "passive"))
      (node (ref "SD1") (pin "4") (pinfunction "VDD_4") (pintype "bidirectional"))
      (node (ref "U2") (pin "2") (pinfunction "3V3_2") (pintype "bidirectional"))
      (node (ref "U8") (pin "1") (pinfunction "VDD_1") (pintype "bidirectional"))
    )
    (net (code "2") (name "/1V2") (class "Default")
      (node (ref "C13") (pin "2") (pinfunction "2_2") (pintype "passive"))
      (node (ref "C20") (pin "1") (pinfunction "1_1") (pintype "passive"))
      (node (ref "C24") (pin "1") (pinfunction "1_1") (pintype "passive"))
      (node (ref "J5") (pin "10") (pinfunction "DVDD1_2_10") (pintype "bidirectional"))
      (node (ref "U7") (pin "2") (pinfunction "VOUT_2") (pintype "bidirectional"))
    )
    (net (code "3") (name "/2V8") (class "Default")
      (node (ref "C11") (pin "2") (pinfunction "2_2") (pintype "passive"))
      (node (ref "C12") (pin "1") (pinfunction "1_1") (pintype "passive"))
      (node (ref "C17") (pin "1") (pinfunction "1_1") (pintype "passive"))
      (node (ref "J5") (pin "4") (pinfunction "AVDD2_8_4") (pintype "bidirectional"))
      (node (ref "R26") (pin "2") (pinfunction "2_2") (pintype "passive"))
      (node (ref "U5") (pin "2") (pinfunction "VOUT_2") (pintype "bidirectional"))
    )
    (net (code "4") (name "/3V3_1") (class "Default")
      (node (ref "C15") (pin "2") (pinfunction "2_2") (pintype "passive"))
      (node (ref "R39") (pin "1") (pinfunction "1_1") (pintype "passive"))
      (node (ref "R68") (pin "2") (pinfunction "2_2") (pintype "passive"))
      (node (ref "U28") (pin "7") (pinfunction "VDD_7") (pintype "bidirectional"))
      (node (ref "U28") (pin "8") (pinfunction "CHIPEN_8") (pintype "bidirectional"))
    )
    (net (code "5") (name "/3V3_CAM") (class "Default")
      (node (ref "B2") (pin "1") (pinfunction "1_1") (pintype "passive"))
      (node (ref "C18") (pin "2") (pinfunction "2_2") (pintype "passive"))
      (node (ref "C19") (pin "2") (pinfunction "2_2") (pintype "passive"))
      (node (ref "U5") (pin "3") (pinfunction "VIN_3") (pintype "bidirectional"))
      (node (ref "U7") (pin "3") (pinfunction "VIN_3") (pintype "bidirectional"))
    )
    (net (code "6") (name "/5V") (class "Default")
      (node (ref "C27") (pin "2") (pinfunction "2_2") (pintype "passive"))
      (node (ref "C29") (pin "2") (pinfunction "2_2") (pintype "passive"))
      (node (ref "C31") (pin "2") (pinfunction "2_2") (pintype "passive"))
      (node (ref "C32") (pin "1") (pinfunction "1_1") (pintype "passive"))
      (node (ref "C33") (pin "1") (pinfunction "1_1") (pintype "passive"))
      (node (ref "C34") (pin "1") (pinfunction "1_1") (pintype "passive"))
      (node (ref "D24") (pin "2") (pinfunction "-_2") (pintype "passive"))
      (node (ref "J1") (pin "3") (pinfunction "3_3") (pintype "bidirectional"))
      (node (ref "J2") (pin "3") (pinfunction "3_3") (pintype "bidirectional"))
      (node (ref "J6") (pin "3") (pinfunction "3_3") (pintype "bidirectional"))
      (node (ref "J8") (pin "3") (pinfunction "3_3") (pintype "bidirectional"))
      (node (ref "R27") (pin "1") (pinfunction "1_1") (pintype "passive"))
      (node (ref "R29") (pin "1") (pinfunction "1_1") (pintype "passive"))
      (node (ref "R36") (pin "1") (pinfunction "1_1") (pintype "passive"))
      (node (ref "R41") (pin "1") (pinfunction "1_1") (pintype "passive"))
      (node (ref "R45") (pin "1") (pinfunction "1_1") (pintype "passive"))
      (node (ref "R47") (pin "1") (pinfunction "1_1") (pintype "passive"))
      (node (ref "R50") (pin "1") (pinfunction "1_1") (pintype "passive"))
    )
    (net (code "7") (name "/A_IO19") (class "Default")
      (node (ref "J3") (pin "1") (pinfunction "1_1") (pintype "bidirectional"))
      (node (ref "U2") (pin "13") (pinfunction "IO19_13") (pintype "bidirectional"))
    )
    (net (code "8") (name "/A_IO20") (class "Default")
      (node (ref "J4") (pin "1") (pinfunction "1_1") (pintype "bidirectional"))
      (node (ref "U2") (pin "14") (pinfunction "IO20_14") (pintype "bidirectional"))
    )
    (net (code "9") (name "/BAT_DET") (class "Default")
      (node (ref "R17") (pin "2") (pinfunction "2_2") (pintype "passive"))
      (node (ref "R18") (pin "1") (pinfunction "1_1") (pintype "passive"))
      (node (ref "U2") (pin "17") (pinfunction "IO9_SD2_17") (pintype "bidirectional"))
    )
    (net (code "10") (name "/BUZZER_IO45") (class "Default")
      (node (ref "R53") (pin "1") (pinfunction "1_1") (pintype "passive"))
      (node (ref "R6") (pin "2") (pinfunction "2_2") (pintype "passive"))
      (node (ref "U2") (pin "26") (pinfunction "IO45_26") (pintype "bidirectional"))
    )
    (net (code "11") (name "/CAM-MCLK") (class "Default")
      (node (ref "J5") (pin "13") (pinfunction "13MCLK_13") (pintype "bidirectional"))
      (node (ref "U2") (pin "7") (pinfunction "IO7_7") (pintype "bidirectional"))
    )
    (net (code "12") (name "/CAM_D2") (class "Default")
      (node (ref "J5") (pin "19") (pinfunction "19D2_19") (pintype "bidirectional"))
      (node (ref "U2") (pin "12") (pinfunction "IO8_12") (pintype "bidirectional"))
    )
    (net (code "13") (name "/CAM_D3") (class "Default")
      (node (ref "J5") (pin "21") (pinfunction "21D3_21") (pintype "bidirectional"))
      (node (ref "U2") (pin "24") (pinfunction "IO47_24") (pintype "bidirectional"))
    )
    (net (code "14") (name "/CAM_D4") (class "Default")
      (node (ref "J5") (pin "22") (pinfunction "22D4_22") (pintype "bidirectional"))
      (node (ref "U2") (pin "25") (pinfunction "IO48_25") (pintype "bidirectional"))
    )
    (net (code "15") (name "/CAM_D5") (class "Default")
      (node (ref "J5") (pin "20") (pinfunction "20D5_20") (pintype "bidirectional"))
      (node (ref "U2") (pin "23") (pinfunction "IO21_23") (pintype "bidirectional"))
    )
    (net (code "16") (name "/CAM_D6") (class "Default")
      (node (ref "J5") (pin "18") (pinfunction "18D6_18") (pintype "bidirectional"))
      (node (ref "U2") (pin "11") (pinfunction "IO18_11") (pintype "bidirectional"))
    )
    (net (code "17") (name "/CAM_D7") (class "Default")
      (node (ref "J5") (pin "16") (pinfunction "16D7_16") (pintype "bidirectional"))
      (node (ref "U2") (pin "9") (pinfunction "IO16_9") (pintype "bidirectional"))
    )
    (net (code "18") (name "/CAM_D8") (class "Default")
      (node (ref "J5") (pin "14") (pinfunction "14D8_14") (pintype "bidirectional"))
      (node (ref "U2") (pin "8") (pinfunction "IO15_8") (pintype "bidirectional"))
    )
    (net (code "19") (name "/CAM_D9") (class "Default")
      (node (ref "J5") (pin "12") (pinfunction "12D9_12") (pintype "bidirectional"))
      (node (ref "U2") (pin "6") (pinfunction "IO6_6") (pintype "bidirectional"))
    )
    (net (code "20") (name "/CAM_PCLK") (class "Default")
      (node (ref "J5") (pin "17") (pinfunction "17PCLCK_17") (pintype "bidirectional"))
      (node (ref "U2") (pin "10") (pinfunction "IO17_10") (pintype "bidirectional"))
    )
    (net (code "21") (name "/D+") (class "Default")
      (node (ref "J7") (pin "A6") (pinfunction "A6_A6") (pintype "bidirectional"))
      (node (ref "J7") (pin "B6") (pinfunction "B6_B6") (pintype "bidirectional"))
      (node (ref "R46") (pin "1") (pinfunction "1_1") (pintype "passive"))
    )
    (net (code "22") (name "/D-") (class "Default")
      (node (ref "J7") (pin "A7") (pinfunction "A7_A7") (pintype "bidirectional"))
      (node (ref "J7") (pin "B7") (pinfunction "B7_B7") (pintype "bidirectional"))
      (node (ref "R5") (pin "1") (pinfunction "1_1") (pintype "passive"))
    )
    (net (code "23") (name "/DOWNL_IO0") (class "Default")
      (node (ref "K2") (pin "1") (pinfunction "1_1") (pintype "passive"))
      (node (ref "R13") (pin "2") (pinfunction "2_2") (pintype "passive"))
      (node (ref "U2") (pin "27") (pinfunction "IO0_27") (pintype "bidirectional"))
    )
    (net (code "24") (name "/D_IO11") (class "Default")
      (node (ref "Q7") (pin "2") (pinfunction "S_2") (pintype "passive"))
      (node (ref "U2") (pin "19") (pinfunction "IO11_CMD_19") (pintype "bidirectional"))
    )
    (net (code "25") (name "/D_IO11_1") (class "Default")
      (node (ref "J2") (pin "1") (pinfunction "1_1") (pintype "bidirectional"))
      (node (ref "Q7") (pin "3") (pinfunction "D_3") (pintype "passive"))
      (node (ref "R41") (pin "2") (pinfunction "2_2") (pintype "passive"))
    )
    (net (code "26") (name "/GHRG") (class "Default")
      (node (ref "R19") (pin "2") (pinfunction "2_2") (pintype "passive"))
      (node (ref "R55") (pin "2") (pinfunction "2_2") (pintype "passive"))
      (node (ref "U10") (pin "1") (pinfunction "CHRG_1") (pintype "bidirectional"))
      (node (ref "U4") (pin "7") (pinfunction "P3.2/SCLK_7") (pintype "bidirectional"))
    )
    (net (code "27") (name "/GPIO40") (class "Default")
      (node (ref "Q6") (pin "2") (pinfunction "S_2") (pintype "passive"))
      (node (ref "R35") (pin "1") (pinfunction "1_1") (pintype "passive"))
      (node (ref "U2") (pin "33") (pinfunction "IO40_33") (pintype "bidirectional"))
    )
    (net (code "28") (name "/GPIO40_1") (class "Default")
      (node (ref "J8") (pin "1") (pinfunction "1_1") (pintype "bidirectional"))
      (node (ref "Q6") (pin "3") (pinfunction "D_3") (pintype "passive"))
      (node (ref "R36") (pin "2") (pinfunction "2_2") (pintype "passive"))
    )
    (net (code "29") (name "/HS") (class "Default")
      (node (ref "J5") (pin "9") (pinfunction "9HSYNC_9") (pintype "bidirectional"))
      (node (ref "U2") (pin "5") (pinfunction "IO5_SENSOR_VN_5") (pintype "bidirectional"))
    )
    (net (code "30") (name "/IO0{slash}LCD_IRQ") (class "Default")
      (node (ref "U8") (pin "7") (pinfunction "PENIRQ_7") (pintype "bidirectional"))
    )
    (net (code "31") (name "/LCD_BACK") (class "Default")
      (node (ref "R15") (pin "2") (pinfunction "2_2") (pintype "passive"))
      (node (ref "U2") (pin "16") (pinfunction "IO46_16") (pintype "bidirectional"))
    )
    (net (code "32") (name "/LCD_SCS") (class "Default")
      (node (ref "J9") (pin "9") (pinfunction "9_9") (pintype "bidirectional"))
      (node (ref "U2") (pin "15") (pinfunction "IO3_15") (pintype "bidirectional"))
    )
    (net (code "33") (name "/LED") (class "Default")
      (node (ref "R54") (pin "2") (pinfunction "2_2") (pintype "passive"))
      (node (ref "U4") (pin "8") (pinfunction "P3.3/MISO_8") (pintype "bidirectional"))
    )
    (net (code "34") (name "/MIC_CLK") (class "Default")
      (node (ref "U2") (pin "32") (pinfunction "IO39_32") (pintype "bidirectional"))
      (node (ref "U28") (pin "1") (pinfunction "SCK_1") (pintype "bidirectional"))
    )
    (net (code "35") (name "/MIC_SD") (class "Default")
      (node (ref "R40") (pin "1") (pinfunction "1_1") (pintype "passive"))
      (node (ref "U2") (pin "34") (pinfunction "IO41_34") (pintype "bidirectional"))
      (node (ref "U28") (pin "2") (pinfunction "SD_2") (pintype "bidirectional"))
    )
    (net (code "36") (name "/MIC_WS") (class "Default")
      (node (ref "U2") (pin "31") (pinfunction "IO38_31") (pintype "bidirectional"))
      (node (ref "U28") (pin "3") (pinfunction "WS1_3") (pintype "bidirectional"))
    )
    (net (code "37") (name "/MISO") (class "Default")
      (node (ref "D6") (pin "+") (pinfunction "+_+") (pintype "passive"))
      (node (ref "J9") (pin "14") (pinfunction "14_14") (pintype "bidirectional"))
    )
    (net (code "38") (name "/RESET") (class "Default")
      (node (ref "C2") (pin "2") (pinfunction "2_2") (pintype "passive"))
      (node (ref "J10") (pin "5") (pinfunction "5_5") (pintype "bidirectional"))
      (node (ref "J5") (pin "6") (pinfunction "6RESET_6") (pintype "bidirectional"))
      (node (ref "J9") (pin "15") (pinfunction "15_15") (pintype "bidirectional"))
      (node (ref "K1") (pin "2") (pinfunction "2_2") (pintype "passive"))
      (node (ref "R3") (pin "1") (pinfunction "1_1") (pintype "passive"))
      (node (ref "U2") (pin "3") (pinfunction "EN_3") (pintype "bidirectional"))
    )
    (net (code "39") (name "/RXD") (class "Default")
      (node (ref "J7") (pin "A5") (pinfunction "A5_A5") (pintype "bidirectional"))
      (node (ref "J7") (pin "B5") (pinfunction "B5_B5") (pintype "bidirectional"))
      (node (ref "R9") (pin "1") (pinfunction "1_1") (pintype "passive"))
    )
    (net (code "40") (name "/SCL") (class "Default")
      (node (ref "J10") (pin "3") (pinfunction "3_3") (pintype "bidirectional"))
      (node (ref "J5") (pin "5") (pinfunction "5SCL_5") (pintype "bidirectional"))
      (node (ref "Q404") (pin "2") (pinfunction "S_2") (pintype "passive"))
      (node (ref "R44") (pin "1") (pinfunction "1_1") (pintype "passive"))
      (node (ref "U2") (pin "39") (pinfunction "IO1_39") (pintype "bidirectional"))
      (node (ref "U8") (pin "10") (pinfunction "SCL_10") (pintype "bidirectional"))
    )
    (net (code "41") (name "/SCL_1") (class "Default")
      (node (ref "J1") (pin "1") (pinfunction "1_1") (pintype "bidirectional"))
      (node (ref "Q404") (pin "3") (pinfunction "D_3") (pintype "passive"))
      (node (ref "R45") (pin "2") (pinfunction "2_2") (pintype "passive"))
    )
    (net (code "42") (name "/SDA") (class "Default")
      (node (ref "J10") (pin "2") (pinfunction "2_2") (pintype "bidirectional"))
      (node (ref "J5") (pin "3") (pinfunction "3SDA_3") (pintype "bidirectional"))
      (node (ref "Q403") (pin "2") (pinfunction "S_2") (pintype "passive"))
      (node (ref "R43") (pin "1") (pinfunction "1_1") (pintype "passive"))
      (node (ref "U2") (pin "38") (pinfunction "IO2_38") (pintype "bidirectional"))
      (node (ref "U8") (pin "9") (pinfunction "SDA_9") (pintype "bidirectional"))
    )
    (net (code "43") (name "/SDA_1") (class "Default")
      (node (ref "J1") (pin "2") (pinfunction "2_2") (pintype "bidirectional"))
      (node (ref "Q403") (pin "3") (pinfunction "D_3") (pintype "passive"))
      (node (ref "R47") (pin "2") (pinfunction "2_2") (pintype "passive"))
    )
    (net (code "44") (name "/SPI_D{slash}I") (class "Default")
      (node (ref "J9") (pin "10") (pinfunction "10_10") (pintype "bidirectional"))
      (node (ref "R34") (pin "2") (pinfunction "2_2") (pintype "passive"))
      (node (ref "U2") (pin "35") (pinfunction "IO42_35") (pintype "bidirectional"))
    )
    (net (code "45") (name "/SPI_IO0") (class "Default")
      (node (ref "D4") (pin "1") (pinfunction "1_1") (pintype "bidirectional"))
      (node (ref "J9") (pin "13") (pinfunction "13_13") (pintype "bidirectional"))
      (node (ref "R16") (pin "1") (pinfunction "1_1") (pintype "passive"))
      (node (ref "SD1") (pin "3") (pinfunction "DI_3") (pintype "bidirectional"))
    )
    (net (code "46") (name "/SPI_IO1") (class "Default")
      (node (ref "D6") (pin "-") (pinfunction "-_-") (pintype "passive"))
      (node (ref "D7") (pin "1") (pinfunction "1_1") (pintype "bidirectional"))
      (node (ref "R24") (pin "1") (pinfunction "1_1") (pintype "passive"))
      (node (ref "SD1") (pin "7") (pinfunction "DO_7") (pintype "bidirectional"))
    )
    (net (code "47") (name "/SPI_SCL") (class "Default")
      (node (ref "D5") (pin "1") (pinfunction "1_1") (pintype "bidirectional"))
      (node (ref "J9") (pin "11") (pinfunction "11_11") (pintype "bidirectional"))
      (node (ref "SD1") (pin "5") (pinfunction "SCLK_5") (pintype "bidirectional"))
      (node (ref "U2") (pin "20") (pinfunction "IO12_CLK_20") (pintype "bidirectional"))
    )
    (net (code "48") (name "/TF_CS") (class "Default")
      (node (ref "D13") (pin "1") (pinfunction "1_1") (pintype "bidirectional"))
      (node (ref "R67") (pin "2") (pinfunction "2_2") (pintype "passive"))
      (node (ref "SD1") (pin "2") (pinfunction "CS_2") (pintype "bidirectional"))
      (node (ref "U2") (pin "18") (pinfunction "IO10_SD3_18") (pintype "bidirectional"))
    )
    (net (code "49") (name "/TXD") (class "Default")
      (node (ref "J7") (pin "A8") (pinfunction "A8_A8") (pintype "bidirectional"))
      (node (ref "J7") (pin "B8") (pinfunction "B8_B8") (pintype "bidirectional"))
      (node (ref "R8") (pin "1") (pinfunction "1_1") (pintype "passive"))
    )
    (net (code "50") (name "/UART0_RXD0") (class "Default")
      (node (ref "Q4") (pin "2") (pinfunction "S_2") (pintype "passive"))
      (node (ref "R72") (pin "1") (pinfunction "1_1") (pintype "passive"))
      (node (ref "U2") (pin "36") (pinfunction "RXD0_36") (pintype "bidirectional"))
    )
    (net (code "51") (name "/UART0_RXD01") (class "Default")
      (node (ref "J6") (pin "1") (pinfunction "1_1") (pintype "bidirectional"))
      (node (ref "Q4") (pin "3") (pinfunction "D_3") (pintype "passive"))
      (node (ref "R29") (pin "2") (pinfunction "2_2") (pintype "passive"))
    )
    (net (code "52") (name "/UART0_TXD0") (class "Default")
      (node (ref "Q3") (pin "2") (pinfunction "S_2") (pintype "passive"))
      (node (ref "R71") (pin "1") (pinfunction "1_1") (pintype "passive"))
      (node (ref "U2") (pin "37") (pinfunction "TXD0_37") (pintype "bidirectional"))
    )
    (net (code "53") (name "/UART0_TXD01") (class "Default")
      (node (ref "J6") (pin "2") (pinfunction "2_2") (pintype "bidirectional"))
      (node (ref "Q3") (pin "3") (pinfunction "D_3") (pintype "passive"))
      (node (ref "R27") (pin "2") (pinfunction "2_2") (pintype "passive"))
    )
    (net (code "54") (name "/USB_D+") (class "Default")
      (node (ref "R46") (pin "2") (pinfunction "2_2") (pintype "passive"))
      (node (ref "U6") (pin "5") (pinfunction "UD+_5") (pintype "bidirectional"))
    )
    (net (code "55") (name "/USB_D-") (class "Default")
      (node (ref "R5") (pin "2") (pinfunction "2_2") (pintype "passive"))
      (node (ref "U6") (pin "6") (pinfunction "UD-_6") (pintype "bidirectional"))
    )
    (net (code "56") (name "/VBAT_VCC") (class "Default")
      (node (ref "BAT") (pin "1") (pinfunction "1_1") (pintype "bidirectional"))
      (node (ref "C21") (pin "2") (pinfunction "2_2") (pintype "passive"))
      (node (ref "Q1") (pin "3") (pinfunction "D_3") (pintype "passive"))
      (node (ref "R17") (pin "1") (pinfunction "1_1") (pintype "passive"))
      (node (ref "U10") (pin "3") (pinfunction "BAT_3") (pintype "bidirectional"))
    )
    (net (code "57") (name "/VBUS") (class "Default")
      (node (ref "C23") (pin "2") (pinfunction "2_2") (pintype "passive"))
      (node (ref "C6") (pin "2") (pinfunction "2_2") (pintype "passive"))
      (node (ref "CHR") (pin "+") (pinfunction "+_+") (pintype "passive"))
      (node (ref "D2") (pin "A") (pinfunction "+_A") (pintype "passive"))
      (node (ref "J7") (pin "A4") (pinfunction "A4_A4") (pintype "bidirectional"))
      (node (ref "J7") (pin "A9") (pinfunction "A9_A9") (pintype "bidirectional"))
      (node (ref "J7") (pin "B4") (pinfunction "B4_B4") (pintype "bidirectional"))
      (node (ref "J7") (pin "B9") (pinfunction "B9_B9") (pintype "bidirectional"))
      (node (ref "R2") (pin "2") (pinfunction "2_2") (pintype "passive"))
      (node (ref "R55") (pin "1") (pinfunction "1_1") (pintype "passive"))
      (node (ref "U10") (pin "4") (pinfunction "VCC_4") (pintype "bidirectional"))
      (node (ref "U4") (pin "2") (pinfunction "VCC_2") (pintype "bidirectional"))
    )
    (net (code "58") (name "/VCC_IN") (class "Default")
      (node (ref "C14") (pin "1") (pinfunction "1_1") (pintype "passive"))
      (node (ref "C22") (pin "2") (pinfunction "2_2") (pintype "passive"))
      (node (ref "C26") (pin "1") (pinfunction "1_1") (pintype "passive"))
      (node (ref "C30") (pin "2") (pinfunction "2_2") (pintype "passive"))
      (node (ref "C43") (pin "2") (pinfunction "2_2") (pintype "passive"))
      (node (ref "C5") (pin "1") (pinfunction "1_1") (pintype "passive"))
      (node (ref "C7") (pin "1") (pinfunction "1_1") (pintype "passive"))
      (node (ref "D2") (pin "C") (pinfunction "-_C") (pintype "passive"))
      (node (ref "L6") (pin "1") (pinfunction "1_1") (pintype "bidirectional"))
      (node (ref "Q1") (pin "2") (pinfunction "S_2") (pintype "passive"))
      (node (ref "U1") (pin "1") (pinfunction "CE_1") (pintype "bidirectional"))
      (node (ref "U1") (pin "4") (pinfunction "VIN_4") (pintype "bidirectional"))
      (node (ref "U3") (pin "4") (pinfunction "4-SHDN_4") (pintype "bidirectional"))
      (node (ref "U3") (pin "5") (pinfunction "5-VIN_5") (pintype "bidirectional"))
      (node (ref "U6") (pin "16") (pinfunction "VCC_16") (pintype "bidirectional"))
    )
    (net (code "59") (name "/VS") (class "Default")
      (node (ref "J5") (pin "7") (pinfunction "7VSYNC_7") (pintype "bidirectional"))
      (node (ref "U2") (pin "4") (pinfunction "IO4_SENSOR_VP_4") (pintype "bidirectional"))
    )
    (net (code "60") (name "/XI") (class "Default")
      (node (ref "U6") (pin "7") (pinfunction "XI_7") (pintype "bidirectional"))
    )
    (net (code "61") (name "/XL") (class "Default")
      (node (ref "J9") (pin "1") (pinfunction "1_1") (pintype "bidirectional"))
      (node (ref "U8") (pin "4") (pinfunction "XN_4") (pintype "bidirectional"))
    )
    (net (code "62") (name "/XO") (class "Default")
      (node (ref "U6") (pin "8") (pinfunction "XO_8") (pintype "bidirectional"))
    )
    (net (code "63") (name "/XR") (class "Default")
      (node (ref "J9") (pin "3") (pinfunction "3_3") (pintype "bidirectional"))
      (node (ref "U8") (pin "2") (pinfunction "XP_2") (pintype "bidirectional"))
    )
    (net (code "64") (name "/YD") (class "Default")
      (node (ref "J9") (pin "4") (pinfunction "4_4") (pintype "bidirectional"))
      (node (ref "U8") (pin "3") (pinfunction "YP_3") (pintype "bidirectional"))
    )
    (net (code "65") (name "/YU") (class "Default")
      (node (ref "J9") (pin "2") (pinfunction "2_2") (pintype "bidirectional"))
      (node (ref "U8") (pin "5") (pinfunction "YN_5") (pintype "bidirectional"))
    )
    (net (code "66") (name "GND") (class "Default")
      (node (ref "BAT") (pin "2") (pinfunction "2_2") (pintype "bidirectional"))
      (node (ref "BAT") (pin "3") (pinfunction "3_3") (pintype "bidirectional"))
      (node (ref "BAT") (pin "4") (pinfunction "4_4") (pintype "bidirectional"))
      (node (ref "C1") (pin "1") (pinfunction "1_1") (pintype "passive"))
      (node (ref "C10") (pin "1") (pinfunction "1_1") (pintype "passive"))
      (node (ref "C11") (pin "1") (pinfunction "1_1") (pintype "passive"))
      (node (ref "C12") (pin "2") (pinfunction "2_2") (pintype "passive"))
      (node (ref "C13") (pin "1") (pinfunction "1_1") (pintype "passive"))
      (node (ref "C14") (pin "2") (pinfunction "2_2") (pintype "passive"))
      (node (ref "C15") (pin "1") (pinfunction "1_1") (pintype "passive"))
      (node (ref "C16") (pin "2") (pinfunction "2_2") (pintype "passive"))
      (node (ref "C17") (pin "2") (pinfunction "2_2") (pintype "passive"))
      (node (ref "C18") (pin "1") (pinfunction "1_1") (pintype "passive"))
      (node (ref "C19") (pin "1") (pinfunction "1_1") (pintype "passive"))
      (node (ref "C2") (pin "1") (pinfunction "1_1") (pintype "passive"))
      (node (ref "C20") (pin "2") (pinfunction "2_2") (pintype "passive"))
      (node (ref "C21") (pin "1") (pinfunction "1_1") (pintype "passive"))
      (node (ref "C22") (pin "1") (pinfunction "1_1") (pintype "passive"))
      (node (ref "C23") (pin "1") (pinfunction "1_1") (pintype "passive"))
      (node (ref "C24") (pin "2") (pinfunction "2_2") (pintype "passive"))
      (node (ref "C26") (pin "2") (pinfunction "2_2") (pintype "passive"))
      (node (ref "C27") (pin "1") (pinfunction "1_1") (pintype "passive"))
      (node (ref "C28") (pin "2") (pinfunction "2_2") (pintype "passive"))
      (node (ref "C29") (pin "1") (pinfunction "1_1") (pintype "passive"))
      (node (ref "C3") (pin "2") (pinfunction "2_2") (pintype "passive"))
      (node (ref "C30") (pin "1") (pinfunction "1_1") (pintype "passive"))
      (node (ref "C31") (pin "1") (pinfunction "1_1") (pintype "passive"))
      (node (ref "C32") (pin "2") (pinfunction "2_2") (pintype "passive"))
      (node (ref "C33") (pin "2") (pinfunction "2_2") (pintype "passive"))
      (node (ref "C34") (pin "2") (pinfunction "2_2") (pintype "passive"))
      (node (ref "C35") (pin "1") (pinfunction "1_1") (pintype "passive"))
      (node (ref "C36") (pin "2") (pinfunction "2_2") (pintype "passive"))
      (node (ref "C37") (pin "1") (pinfunction "1_1") (pintype "passive"))
      (node (ref "C38") (pin "1") (pinfunction "1_1") (pintype "passive"))
      (node (ref "C39") (pin "2") (pinfunction "2_2") (pintype "passive"))
      (node (ref "C4") (pin "2") (pinfunction "2_2") (pintype "passive"))
      (node (ref "C40") (pin "2") (pinfunction "2_2") (pintype "passive"))
      (node (ref "C41") (pin "1") (pinfunction "1_1") (pintype "passive"))
      (node (ref "C42") (pin "1") (pinfunction "1_1") (pintype "passive"))
      (node (ref "C43") (pin "1") (pinfunction "1_1") (pintype "passive"))
      (node (ref "C5") (pin "2") (pinfunction "2_2") (pintype "passive"))
      (node (ref "C54") (pin "1") (pinfunction "1_1") (pintype "passive"))
      (node (ref "C6") (pin "1") (pinfunction "1_1") (pintype "passive"))
      (node (ref "C7") (pin "2") (pinfunction "2_2") (pintype "passive"))
      (node (ref "C8") (pin "1") (pinfunction "1_1") (pintype "passive"))
      (node (ref "C9") (pin "1") (pinfunction "1_1") (pintype "passive"))
      (node (ref "D13") (pin "2") (pinfunction "2_2") (pintype "bidirectional"))
      (node (ref "D4") (pin "2") (pinfunction "2_2") (pintype "bidirectional"))
      (node (ref "D5") (pin "2") (pinfunction "2_2") (pintype "bidirectional"))
      (node (ref "D7") (pin "2") (pinfunction "2_2") (pintype "bidirectional"))
      (node (ref "J1") (pin "4") (pinfunction "4_4") (pintype "bidirectional"))
      (node (ref "J1") (pin "SS1") (pinfunction "SS1_SS1") (pintype "bidirectional"))
      (node (ref "J1") (pin "SS2") (pinfunction "SS2_SS2") (pintype "bidirectional"))
      (node (ref "J10") (pin "6") (pinfunction "6_6") (pintype "bidirectional"))
      (node (ref "J10") (pin "7") (pinfunction "7_7") (pintype "bidirectional"))
      (node (ref "J10") (pin "8") (pinfunction "8_8") (pintype "bidirectional"))
      (node (ref "J2") (pin "4") (pinfunction "4_4") (pintype "bidirectional"))
      (node (ref "J2") (pin "SS1") (pinfunction "SS1_SS1") (pintype "bidirectional"))
      (node (ref "J2") (pin "SS2") (pinfunction "SS2_SS2") (pintype "bidirectional"))
      (node (ref "J3") (pin "4") (pinfunction "4_4") (pintype "bidirectional"))
      (node (ref "J3") (pin "SS1") (pinfunction "SS1_SS1") (pintype "bidirectional"))
      (node (ref "J3") (pin "SS2") (pinfunction "SS2_SS2") (pintype "bidirectional"))
      (node (ref "J4") (pin "4") (pinfunction "4_4") (pintype "bidirectional"))
      (node (ref "J4") (pin "SS1") (pinfunction "SS1_SS1") (pintype "bidirectional"))
      (node (ref "J4") (pin "SS2") (pinfunction "SS2_SS2") (pintype "bidirectional"))
      (node (ref "J5") (pin "15") (pinfunction "15GND_15") (pintype "bidirectional"))
      (node (ref "J5") (pin "2") (pinfunction "2AGND_2") (pintype "bidirectional"))
      (node (ref "J5") (pin "25") (pinfunction "25_25") (pintype "bidirectional"))
      (node (ref "J5") (pin "26") (pinfunction "26_26") (pintype "bidirectional"))
      (node (ref "J6") (pin "4") (pinfunction "4_4") (pintype "bidirectional"))
      (node (ref "J6") (pin "SS1") (pinfunction "SS1_SS1") (pintype "bidirectional"))
      (node (ref "J6") (pin "SS2") (pinfunction "SS2_SS2") (pintype "bidirectional"))
      (node (ref "J7") (pin "A1") (pinfunction "A1_A1") (pintype "bidirectional"))
      (node (ref "J7") (pin "A12") (pinfunction "A12_A12") (pintype "bidirectional"))
      (node (ref "J7") (pin "B1") (pinfunction "B1_B1") (pintype "bidirectional"))
      (node (ref "J7") (pin "B12") (pinfunction "B12_B12") (pintype "bidirectional"))
      (node (ref "J7") (pin "P$1") (pinfunction "P$17_P$1") (pintype "bidirectional"))
      (node (ref "J7") (pin "P$2") (pinfunction "P$18_P$2") (pintype "bidirectional"))
      (node (ref "J7") (pin "P$3") (pinfunction "P$19_P$3") (pintype "bidirectional"))
      (node (ref "J7") (pin "P$4") (pinfunction "P$20_P$4") (pintype "bidirectional"))
      (node (ref "J7") (pin "P$5") (pinfunction "P$21_P$5") (pintype "bidirectional"))
      (node (ref "J8") (pin "4") (pinfunction "4_4") (pintype "bidirectional"))
      (node (ref "J8") (pin "SS1") (pinfunction "SS1_SS1") (pintype "bidirectional"))
      (node (ref "J8") (pin "SS2") (pinfunction "SS2_SS2") (pintype "bidirectional"))
      (node (ref "J9") (pin "16") (pinfunction "16_16") (pintype "bidirectional"))
      (node (ref "J9") (pin "17") (pinfunction "17_17") (pintype "bidirectional"))
      (node (ref "J9") (pin "18") (pinfunction "18_18") (pintype "bidirectional"))
      (node (ref "J9") (pin "19") (pinfunction "19_19") (pintype "bidirectional"))
      (node (ref "J9") (pin "20") (pinfunction "20_20") (pintype "bidirectional"))
      (node (ref "J9") (pin "21") (pinfunction "21_21") (pintype "bidirectional"))
      (node (ref "J9") (pin "22") (pinfunction "22_22") (pintype "bidirectional"))
      (node (ref "J9") (pin "23") (pinfunction "23_23") (pintype "bidirectional"))
      (node (ref "J9") (pin "24") (pinfunction "24_24") (pintype "bidirectional"))
      (node (ref "J9") (pin "25") (pinfunction "25_25") (pintype "bidirectional"))
      (node (ref "J9") (pin "26") (pinfunction "26_26") (pintype "bidirectional"))
      (node (ref "J9") (pin "27") (pinfunction "27_27") (pintype "bidirectional"))
      (node (ref "J9") (pin "28") (pinfunction "28_28") (pintype "bidirectional"))
      (node (ref "J9") (pin "29") (pinfunction "29_29") (pintype "bidirectional"))
      (node (ref "J9") (pin "30") (pinfunction "30_30") (pintype "bidirectional"))
      (node (ref "J9") (pin "31") (pinfunction "31_31") (pintype "bidirectional"))
      (node (ref "J9") (pin "32") (pinfunction "32_32") (pintype "bidirectional"))
      (node (ref "J9") (pin "37") (pinfunction "37_37") (pintype "bidirectional"))
      (node (ref "J9") (pin "41") (pinfunction "41_41") (pintype "bidirectional"))
      (node (ref "J9") (pin "42") (pinfunction "42_42") (pintype "bidirectional"))
      (node (ref "J9") (pin "5") (pinfunction "5_5") (pintype "bidirectional"))
      (node (ref "K1") (pin "1") (pinfunction "1_1") (pintype "passive"))
      (node (ref "K2") (pin "2") (pinfunction "2_2") (pintype "passive"))
      (node (ref "NC/R16") (pin "1") (pinfunction "1_1") (pintype "passive"))
      (node (ref "P3") (pin "1") (pinfunction "P$1_1") (pintype "bidirectional"))
      (node (ref "P4") (pin "1") (pinfunction "P$1_1") (pintype "bidirectional"))
      (node (ref "PWR") (pin "-") (pinfunction "-_-") (pintype "passive"))
      (node (ref "Q5") (pin "2") (pinfunction "E_2") (pintype "passive"))
      (node (ref "Q8") (pin "2") (pinfunction "E_2") (pintype "passive"))
      (node (ref "R18") (pin "2") (pinfunction "2_2") (pintype "passive"))
      (node (ref "R21") (pin "2") (pinfunction "2_2") (pintype "passive"))
      (node (ref "R23") (pin "1") (pinfunction "1_1") (pintype "passive"))
      (node (ref "R25") (pin "2") (pinfunction "2_2") (pintype "passive"))
      (node (ref "R31") (pin "1") (pinfunction "1_1") (pintype "passive"))
      (node (ref "R34") (pin "1") (pinfunction "1_1") (pintype "passive"))
      (node (ref "R4") (pin "2") (pinfunction "2_2") (pintype "passive"))
      (node (ref "R40") (pin "2") (pinfunction "2_2") (pintype "passive"))
      (node (ref "R48") (pin "1") (pinfunction "1_1") (pintype "passive"))
      (node (ref "R49") (pin "1") (pinfunction "1_1") (pintype "passive"))
      (node (ref "R51") (pin "2") (pinfunction "2_2") (pintype "passive"))
      (node (ref "R6") (pin "1") (pinfunction "1_1") (pintype "passive"))
      (node (ref "SD1") (pin "6") (pinfunction "VSS_6") (pintype "bidirectional"))
      (node (ref "SD1") (pin "G1") (pinfunction "G1_G1") (pintype "bidirectional"))
      (node (ref "SD1") (pin "G2") (pinfunction "G2_G2") (pintype "bidirectional"))
      (node (ref "SD1") (pin "G3") (pinfunction "G3_G3") (pintype "bidirectional"))
      (node (ref "SD1") (pin "G4") (pinfunction "G4_G4") (pintype "bidirectional"))
      (node (ref "U1") (pin "2") (pinfunction "GND_2") (pintype "bidirectional"))
      (node (ref "U10") (pin "2") (pinfunction "GND_2") (pintype "bidirectional"))
      (node (ref "U2") (pin "1") (pinfunction "GND_1") (pintype "bidirectional"))
      (node (ref "U2") (pin "40") (pinfunction "GND_40") (pintype "bidirectional"))
      (node (ref "U2") (pin "41") (pinfunction "GND1_41") (pintype "bidirectional"))
      (node (ref "U2") (pin "42") (pinfunction "GND2_42") (pintype "bidirectional"))
      (node (ref "U2") (pin "43") (pinfunction "GND3_43") (pintype "bidirectional"))
      (node (ref "U2") (pin "44") (pinfunction "GND4_44") (pintype "bidirectional"))
      (node (ref "U2") (pin "45") (pinfunction "GND5_45") (pintype "bidirectional"))
      (node (ref "U2") (pin "46") (pinfunction "GND6_46") (pintype "bidirectional"))
      (node (ref "U2") (pin "47") (pinfunction "GND7_47") (pintype "bidirectional"))
      (node (ref "U2") (pin "48") (pinfunction "GND8_48") (pintype "bidirectional"))
      (node (ref "U2") (pin "49") (pinfunction "GND9_49") (pintype "bidirectional"))
      (node (ref "U28") (pin "5") (pinfunction "GND2_5") (pintype "bidirectional"))
      (node (ref "U28") (pin "6") (pinfunction "GND_6") (pintype "bidirectional"))
      (node (ref "U28") (pin "9") (pinfunction "GND1_9") (pintype "bidirectional"))
      (node (ref "U3") (pin "2") (pinfunction "2-GND_2") (pintype "bidirectional"))
      (node (ref "U4") (pin "4") (pinfunction "GND_4") (pintype "bidirectional"))
      (node (ref "U4") (pin "P$9") (pinfunction "GND9_P$9") (pintype "bidirectional"))
      (node (ref "U5") (pin "1") (pinfunction "VSS_1") (pintype "bidirectional"))
      (node (ref "U6") (pin "1") (pinfunction "GND_1") (pintype "bidirectional"))
      (node (ref "U7") (pin "1") (pinfunction "VSS_1") (pintype "bidirectional"))
      (node (ref "U8") (pin "6") (pinfunction "GND_6") (pintype "bidirectional"))
    )
    (net (code "67") (name "Net-(B1-+)") (class "Default")
      (node (ref "B1") (pin "1") (pinfunction "+_1") (pintype "bidirectional"))
      (node (ref "D1") (pin "1") (pinfunction "-_1") (pintype "bidirectional"))
      (node (ref "R42") (pin "2") (pinfunction "2_2") (pintype "passive"))
    )
    (net (code "68") (name "Net-(B1--)") (class "Default")
      (node (ref "B1") (pin "2") (pinfunction "-_2") (pintype "bidirectional"))
      (node (ref "D1") (pin "2") (pinfunction "+_2") (pintype "bidirectional"))
      (node (ref "Q8") (pin "3") (pinfunction "C_3") (pintype "passive"))
    )
    (net (code "69") (name "Net-(CHR-Pad-)") (class "Default")
      (node (ref "CHR") (pin "-") (pinfunction "-_-") (pintype "passive"))
      (node (ref "R19") (pin "1") (pinfunction "1_1") (pintype "passive"))
      (node (ref "R54") (pin "1") (pinfunction "1_1") (pintype "passive"))
    )
    (net (code "70") (name "Net-(D24-+)") (class "Default")
      (node (ref "D24") (pin "1") (pinfunction "+_1") (pintype "passive"))
      (node (ref "L6") (pin "2") (pinfunction "2_2") (pintype "bidirectional"))
      (node (ref "U3") (pin "1") (pinfunction "1-SW_1") (pintype "bidirectional"))
    )
    (net (code "71") (name "Net-(J5-8PWDN)") (class "Default")
      (node (ref "J5") (pin "8") (pinfunction "8PWDN_8") (pintype "bidirectional"))
      (node (ref "R23") (pin "2") (pinfunction "2_2") (pintype "passive"))
    )
    (net (code "72") (name "Net-(J5-DVDD2_8)") (class "Default")
      (node (ref "C16") (pin "1") (pinfunction "1_1") (pintype "passive"))
      (node (ref "J5") (pin "11") (pinfunction "DVDD2_8_11") (pintype "bidirectional"))
      (node (ref "R26") (pin "1") (pinfunction "1_1") (pintype "passive"))
      (node (ref "R28") (pin "1") (pinfunction "1_1") (pintype "passive"))
    )
    (net (code "73") (name "Net-(J9-Pad34)") (class "Default")
      (node (ref "J9") (pin "34") (pinfunction "34_34") (pintype "bidirectional"))
      (node (ref "R7") (pin "2") (pinfunction "2_2") (pintype "passive"))
    )
    (net (code "74") (name "Net-(J9-Pad35)") (class "Default")
      (node (ref "J9") (pin "35") (pinfunction "35_35") (pintype "bidirectional"))
      (node (ref "R10") (pin "2") (pinfunction "2_2") (pintype "passive"))
    )
    (net (code "75") (name "Net-(J9-Pad36)") (class "Default")
      (node (ref "J9") (pin "36") (pinfunction "36_36") (pintype "bidirectional"))
      (node (ref "R11") (pin "2") (pinfunction "2_2") (pintype "passive"))
    )
    (net (code "76") (name "Net-(J9-Pad39)") (class "Default")
      (node (ref "J9") (pin "39") (pinfunction "39_39") (pintype "bidirectional"))
      (node (ref "NC/R16") (pin "2") (pinfunction "2_2") (pintype "passive"))
      (node (ref "R30") (pin "2") (pinfunction "2_2") (pintype "passive"))
    )
    (net (code "77") (name "Net-(J10-Pad4)") (class "Default")
      (node (ref "J10") (pin "4") (pinfunction "4_4") (pintype "bidirectional"))
      (node (ref "R13") (pin "1") (pinfunction "1_1") (pintype "passive"))
    )
    (net (code "78") (name "Net-(PWR-Pad+)") (class "Default")
      (node (ref "PWR") (pin "+") (pinfunction "+_+") (pintype "passive"))
      (node (ref "R1") (pin "1") (pinfunction "1_1") (pintype "passive"))
    )
    (net (code "79") (name "Net-(Q1-G)") (class "Default")
      (node (ref "Q1") (pin "1") (pinfunction "G_1") (pintype "passive"))
      (node (ref "R2") (pin "1") (pinfunction "1_1") (pintype "passive"))
      (node (ref "R4") (pin "1") (pinfunction "1_1") (pintype "passive"))
    )
    (net (code "80") (name "Net-(Q5-B)") (class "Default")
      (node (ref "Q5") (pin "1") (pinfunction "B_1") (pintype "passive"))
      (node (ref "R12") (pin "1") (pinfunction "1_1") (pintype "passive"))
      (node (ref "R15") (pin "1") (pinfunction "1_1") (pintype "passive"))
    )
    (net (code "81") (name "Net-(Q5-C)") (class "Default")
      (node (ref "Q5") (pin "3") (pinfunction "C_3") (pintype "passive"))
      (node (ref "R10") (pin "1") (pinfunction "1_1") (pintype "passive"))
      (node (ref "R11") (pin "1") (pinfunction "1_1") (pintype "passive"))
      (node (ref "R7") (pin "1") (pinfunction "1_1") (pintype "passive"))
    )
    (net (code "82") (name "Net-(Q8-B)") (class "Default")
      (node (ref "Q8") (pin "1") (pinfunction "B_1") (pintype "passive"))
      (node (ref "R53") (pin "2") (pinfunction "2_2") (pintype "passive"))
    )
    (net (code "83") (name "Net-(SD1-DATA1)") (class "Default")
      (node (ref "R20") (pin "2") (pinfunction "2_2") (pintype "passive"))
      (node (ref "SD1") (pin "8") (pinfunction "DATA1_8") (pintype "bidirectional"))
    )
    (net (code "84") (name "Net-(SD1-DATA2)") (class "Default")
      (node (ref "R22") (pin "2") (pinfunction "2_2") (pintype "passive"))
      (node (ref "SD1") (pin "1") (pinfunction "DATA2_1") (pintype "bidirectional"))
    )
    (net (code "85") (name "Net-(U1-BF)") (class "Default")
      (node (ref "R31") (pin "2") (pinfunction "2_2") (pintype "passive"))
      (node (ref "R32") (pin "1") (pinfunction "1_1") (pintype "passive"))
      (node (ref "U1") (pin "5") (pinfunction "BF_5") (pintype "bidirectional"))
    )
    (net (code "86") (name "Net-(U1-LX)") (class "Default")
      (node (ref "L1") (pin "1") (pinfunction "1_1") (pintype "bidirectional"))
      (node (ref "U1") (pin "3") (pinfunction "LX_3") (pintype "bidirectional"))
    )
    (net (code "87") (name "Net-(U2-IO13_SDO)") (class "Default")
      (node (ref "R16") (pin "2") (pinfunction "2_2") (pintype "passive"))
      (node (ref "U2") (pin "21") (pinfunction "IO13_SDO_21") (pintype "bidirectional"))
    )
    (net (code "88") (name "Net-(U2-IO14_SD1)") (class "Default")
      (node (ref "R24") (pin "2") (pinfunction "2_2") (pintype "passive"))
      (node (ref "U2") (pin "22") (pinfunction "IO14_SD1_22") (pintype "bidirectional"))
    )
    (net (code "89") (name "Net-(U3-3-FB)") (class "Default")
      (node (ref "R50") (pin "2") (pinfunction "2_2") (pintype "passive"))
      (node (ref "R51") (pin "1") (pinfunction "1_1") (pintype "passive"))
      (node (ref "U3") (pin "3") (pinfunction "3-FB_3") (pintype "bidirectional"))
    )
    (net (code "90") (name "Net-(U3-6-NC)") (class "Default")
      (node (ref "R48") (pin "2") (pinfunction "2_2") (pintype "passive"))
      (node (ref "U3") (pin "6") (pinfunction "6-NC_6") (pintype "bidirectional"))
    )
    (net (code "91") (name "Net-(U4-P3.0{slash}RXD)") (class "Default")
      (node (ref "P11") (pin "P$1") (pinfunction "P$1_P$1") (pintype "bidirectional"))
      (node (ref "R9") (pin "2") (pinfunction "2_2") (pintype "passive"))
      (node (ref "U4") (pin "5") (pinfunction "P3.0/RXD_5") (pintype "bidirectional"))
    )
    (net (code "92") (name "Net-(U4-P3.1{slash}TXD)") (class "Default")
      (node (ref "P12") (pin "P$1") (pinfunction "P$1_P$1") (pintype "bidirectional"))
      (node (ref "R8") (pin "2") (pinfunction "2_2") (pintype "passive"))
      (node (ref "U4") (pin "6") (pinfunction "P3.1/TXD_6") (pintype "bidirectional"))
    )
    (net (code "93") (name "Net-(U6-RXD)") (class "Default")
      (node (ref "R71") (pin "2") (pinfunction "2_2") (pintype "passive"))
      (node (ref "U6") (pin "3") (pinfunction "RXD_3") (pintype "bidirectional"))
    )
    (net (code "94") (name "Net-(U6-TXD)") (class "Default")
      (node (ref "R72") (pin "2") (pinfunction "2_2") (pintype "passive"))
      (node (ref "U6") (pin "2") (pinfunction "TXD_2") (pintype "bidirectional"))
    )
    (net (code "95") (name "Net-(U6-V3)") (class "Default")
      (node (ref "C1") (pin "2") (pinfunction "2_2") (pintype "passive"))
      (node (ref "U6") (pin "4") (pinfunction "V3_4") (pintype "bidirectional"))
    )
    (net (code "96") (name "Net-(U8-A0)") (class "Default")
      (node (ref "R49") (pin "2") (pinfunction "2_2") (pintype "passive"))
      (node (ref "R52") (pin "1") (pinfunction "1_1") (pintype "passive"))
      (node (ref "U8") (pin "8") (pinfunction "A0_8") (pintype "bidirectional"))
    )
    (net (code "97") (name "Net-(U10-PROG)") (class "Default")
      (node (ref "R21") (pin "1") (pinfunction "1_1") (pintype "passive"))
      (node (ref "U10") (pin "5") (pinfunction "PROG_5") (pintype "bidirectional"))
    )
    (net (code "98") (name "Net-(U28-LR)") (class "Default")
      (node (ref "R25") (pin "1") (pinfunction "1_1") (pintype "passive"))
      (node (ref "R68") (pin "1") (pinfunction "1_1") (pintype "passive"))
      (node (ref "U28") (pin "4") (pinfunction "LR_4") (pintype "bidirectional"))
    )
    (net (code "99") (name "unconnected-(J2-Pad2)") (class "Default")
      (node (ref "J2") (pin "2") (pinfunction "2_2") (pintype "bidirectional"))
    )
    (net (code "100") (name "unconnected-(J3-Pad2)") (class "Default")
      (node (ref "J3") (pin "2") (pinfunction "2_2") (pintype "bidirectional"))
    )
    (net (code "101") (name "unconnected-(J4-Pad2)") (class "Default")
      (node (ref "J4") (pin "2") (pinfunction "2_2") (pintype "bidirectional"))
    )
    (net (code "102") (name "unconnected-(J5-1NC-Pad1)") (class "Default")
      (node (ref "J5") (pin "1") (pinfunction "1NC_1") (pintype "bidirectional"))
    )
    (net (code "103") (name "unconnected-(J5-Pad23)") (class "Default")
      (node (ref "J5") (pin "23") (pinfunction "23_23") (pintype "bidirectional"))
    )
    (net (code "104") (name "unconnected-(J5-Pad24)") (class "Default")
      (node (ref "J5") (pin "24") (pinfunction "24_24") (pintype "bidirectional"))
    )
    (net (code "105") (name "unconnected-(J8-Pad2)") (class "Default")
      (node (ref "J8") (pin "2") (pinfunction "2_2") (pintype "bidirectional"))
    )
    (net (code "106") (name "unconnected-(J9-Pad8)") (class "Default")
      (node (ref "J9") (pin "8") (pinfunction "8_8") (pintype "bidirectional"))
    )
    (net (code "107") (name "unconnected-(P1-PadP$1)") (class "Default")
      (node (ref "P1") (pin "P$1") (pinfunction "P$1_P$1") (pintype "bidirectional"))
    )
    (net (code "108") (name "unconnected-(P5-PadP$1)") (class "Default")
      (node (ref "P5") (pin "P$1") (pinfunction "P$1_P$1") (pintype "bidirectional"))
    )
    (net (code "109") (name "unconnected-(SD1-CDN-Pad9)") (class "Default")
      (node (ref "SD1") (pin "9") (pinfunction "CDN_9") (pintype "bidirectional"))
    )
    (net (code "110") (name "unconnected-(U$63-PadP$1)") (class "Default")
      (node (ref "U$63") (pin "P$1") (pinfunction "P$1_P$1") (pintype "bidirectional"))
    )
    (net (code "111") (name "unconnected-(U2-NC1-Pad28)") (class "Default")
      (node (ref "U2") (pin "28") (pinfunction "NC1_28") (pintype "bidirectional"))
    )
    (net (code "112") (name "unconnected-(U2-NC2-Pad29)") (class "Default")
      (node (ref "U2") (pin "29") (pinfunction "NC2_29") (pintype "bidirectional"))
    )
    (net (code "113") (name "unconnected-(U2-NC3-Pad30)") (class "Default")
      (node (ref "U2") (pin "30") (pinfunction "NC3_30") (pintype "bidirectional"))
    )
    (net (code "114") (name "unconnected-(U4-P5.4{slash}MOSI-Pad1)") (class "Default")
      (node (ref "U4") (pin "1") (pinfunction "P5.4/MOSI_1") (pintype "bidirectional"))
    )
    (net (code "115") (name "unconnected-(U4-P5.5{slash}SS-Pad3)") (class "Default")
      (node (ref "U4") (pin "3") (pinfunction "P5.5/SS_3") (pintype "bidirectional"))
    )
    (net (code "116") (name "unconnected-(U6-CTS#-Pad9)") (class "Default")
      (node (ref "U6") (pin "9") (pinfunction "CTS#_9") (pintype "bidirectional"))
    )
    (net (code "117") (name "unconnected-(U6-DCD#-Pad12)") (class "Default")
      (node (ref "U6") (pin "12") (pinfunction "DCD#_12") (pintype "bidirectional"))
    )
    (net (code "118") (name "unconnected-(U6-DSR#-Pad10)") (class "Default")
      (node (ref "U6") (pin "10") (pinfunction "DSR#_10") (pintype "bidirectional"))
    )
    (net (code "119") (name "unconnected-(U6-DTR#-Pad13)") (class "Default")
      (node (ref "U6") (pin "13") (pinfunction "DTR#_13") (pintype "bidirectional"))
    )
    (net (code "120") (name "unconnected-(U6-RI#-Pad11)") (class "Default")
      (node (ref "U6") (pin "11") (pinfunction "RI#_11") (pintype "bidirectional"))
    )
    (net (code "121") (name "unconnected-(U6-RS232-Pad15)") (class "Default")
      (node (ref "U6") (pin "15") (pinfunction "RS232_15") (pintype "bidirectional"))
    )
    (net (code "122") (name "unconnected-(U6-RTS#-Pad14)") (class "Default")
      (node (ref "U6") (pin "14") (pinfunction "RTS#_14") (pintype "bidirectional"))
    )
  )
)
